# LED-zero20-SHIM.net
KiCad netlist of a schematic drawn in EAGLE
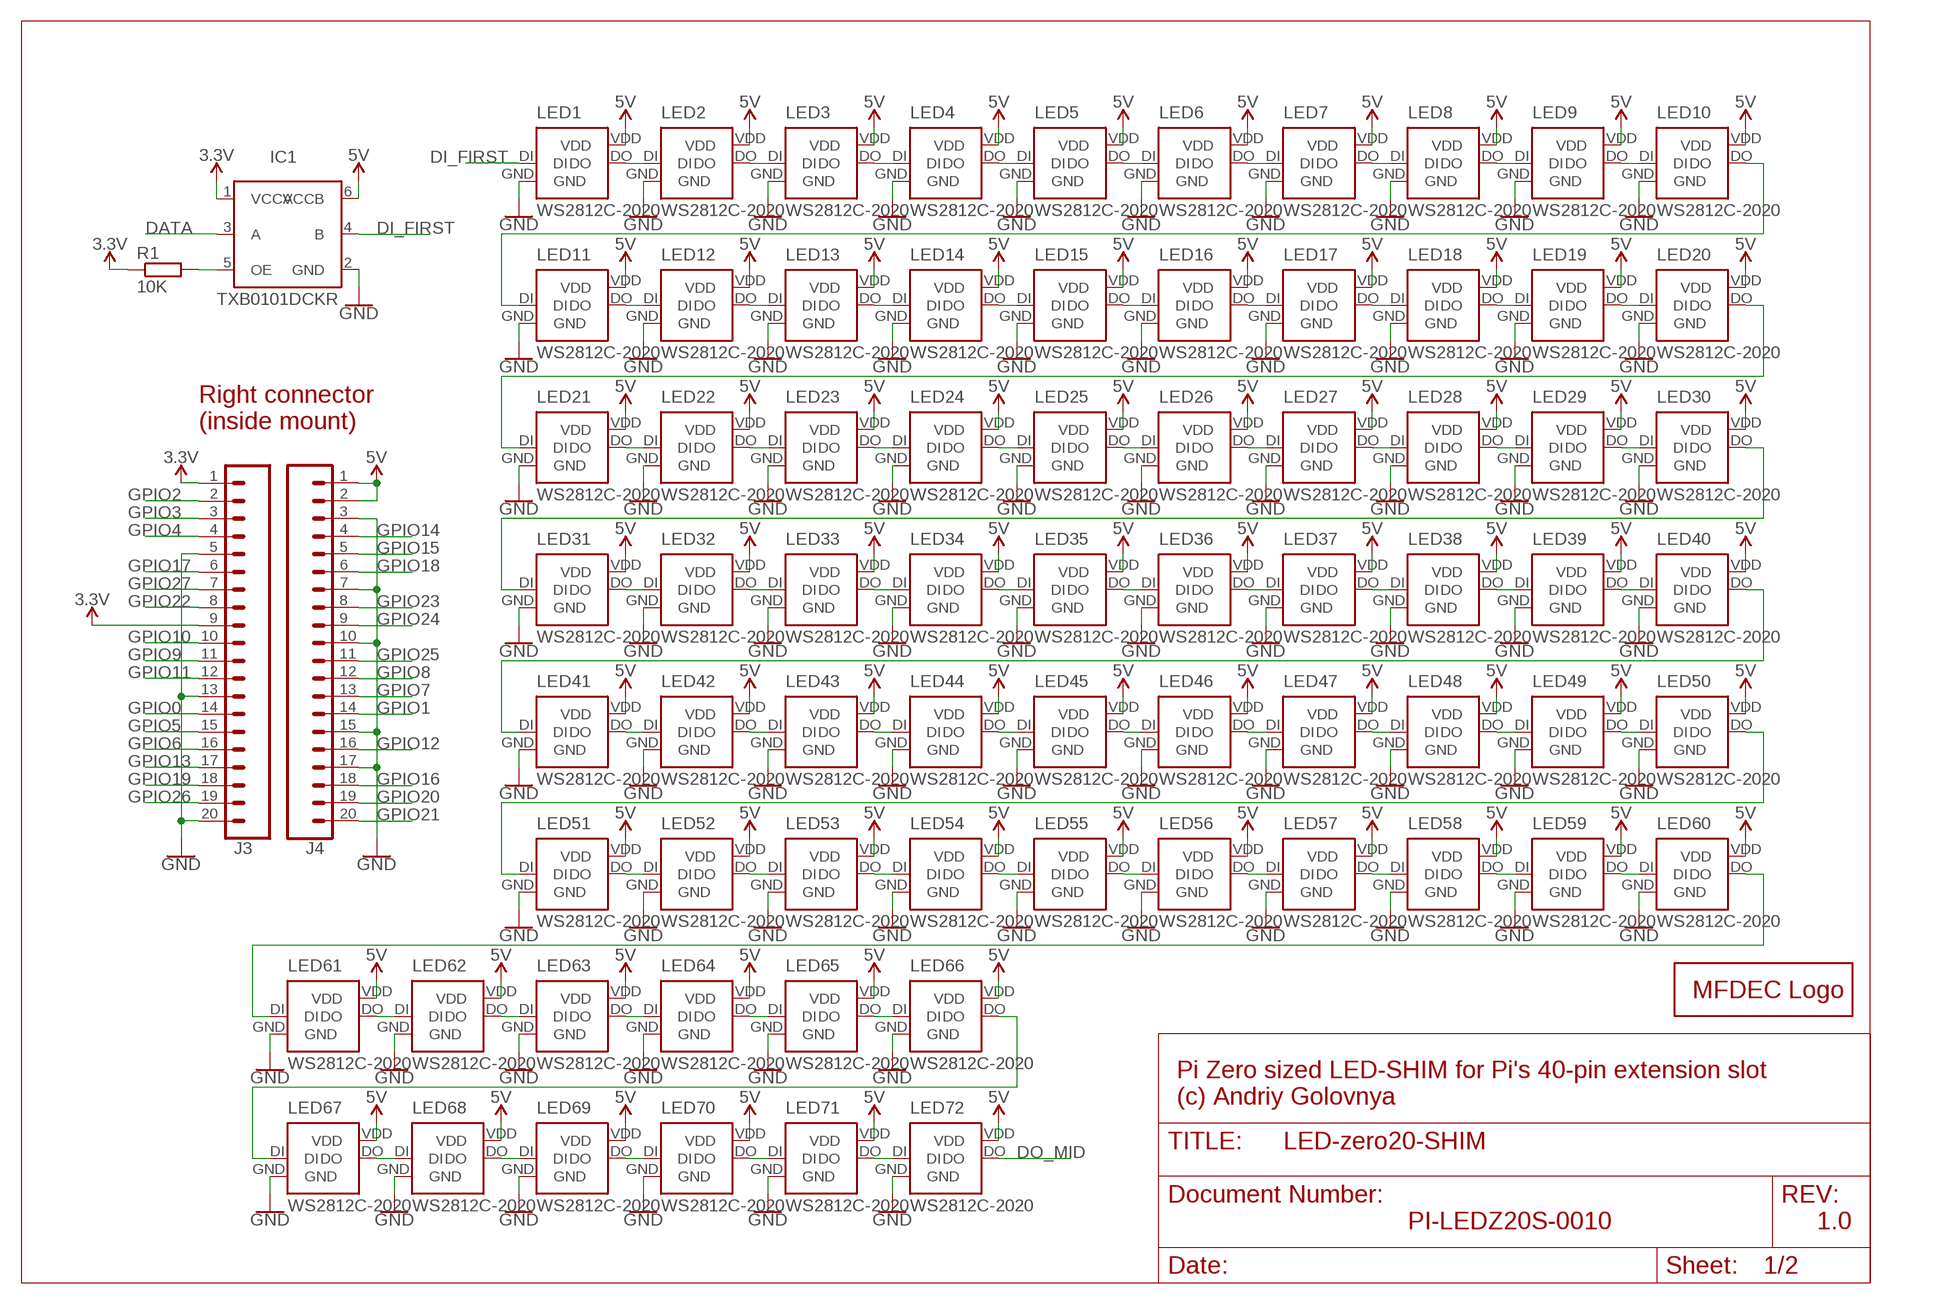
[diagram p0: schematic, sheet 1]
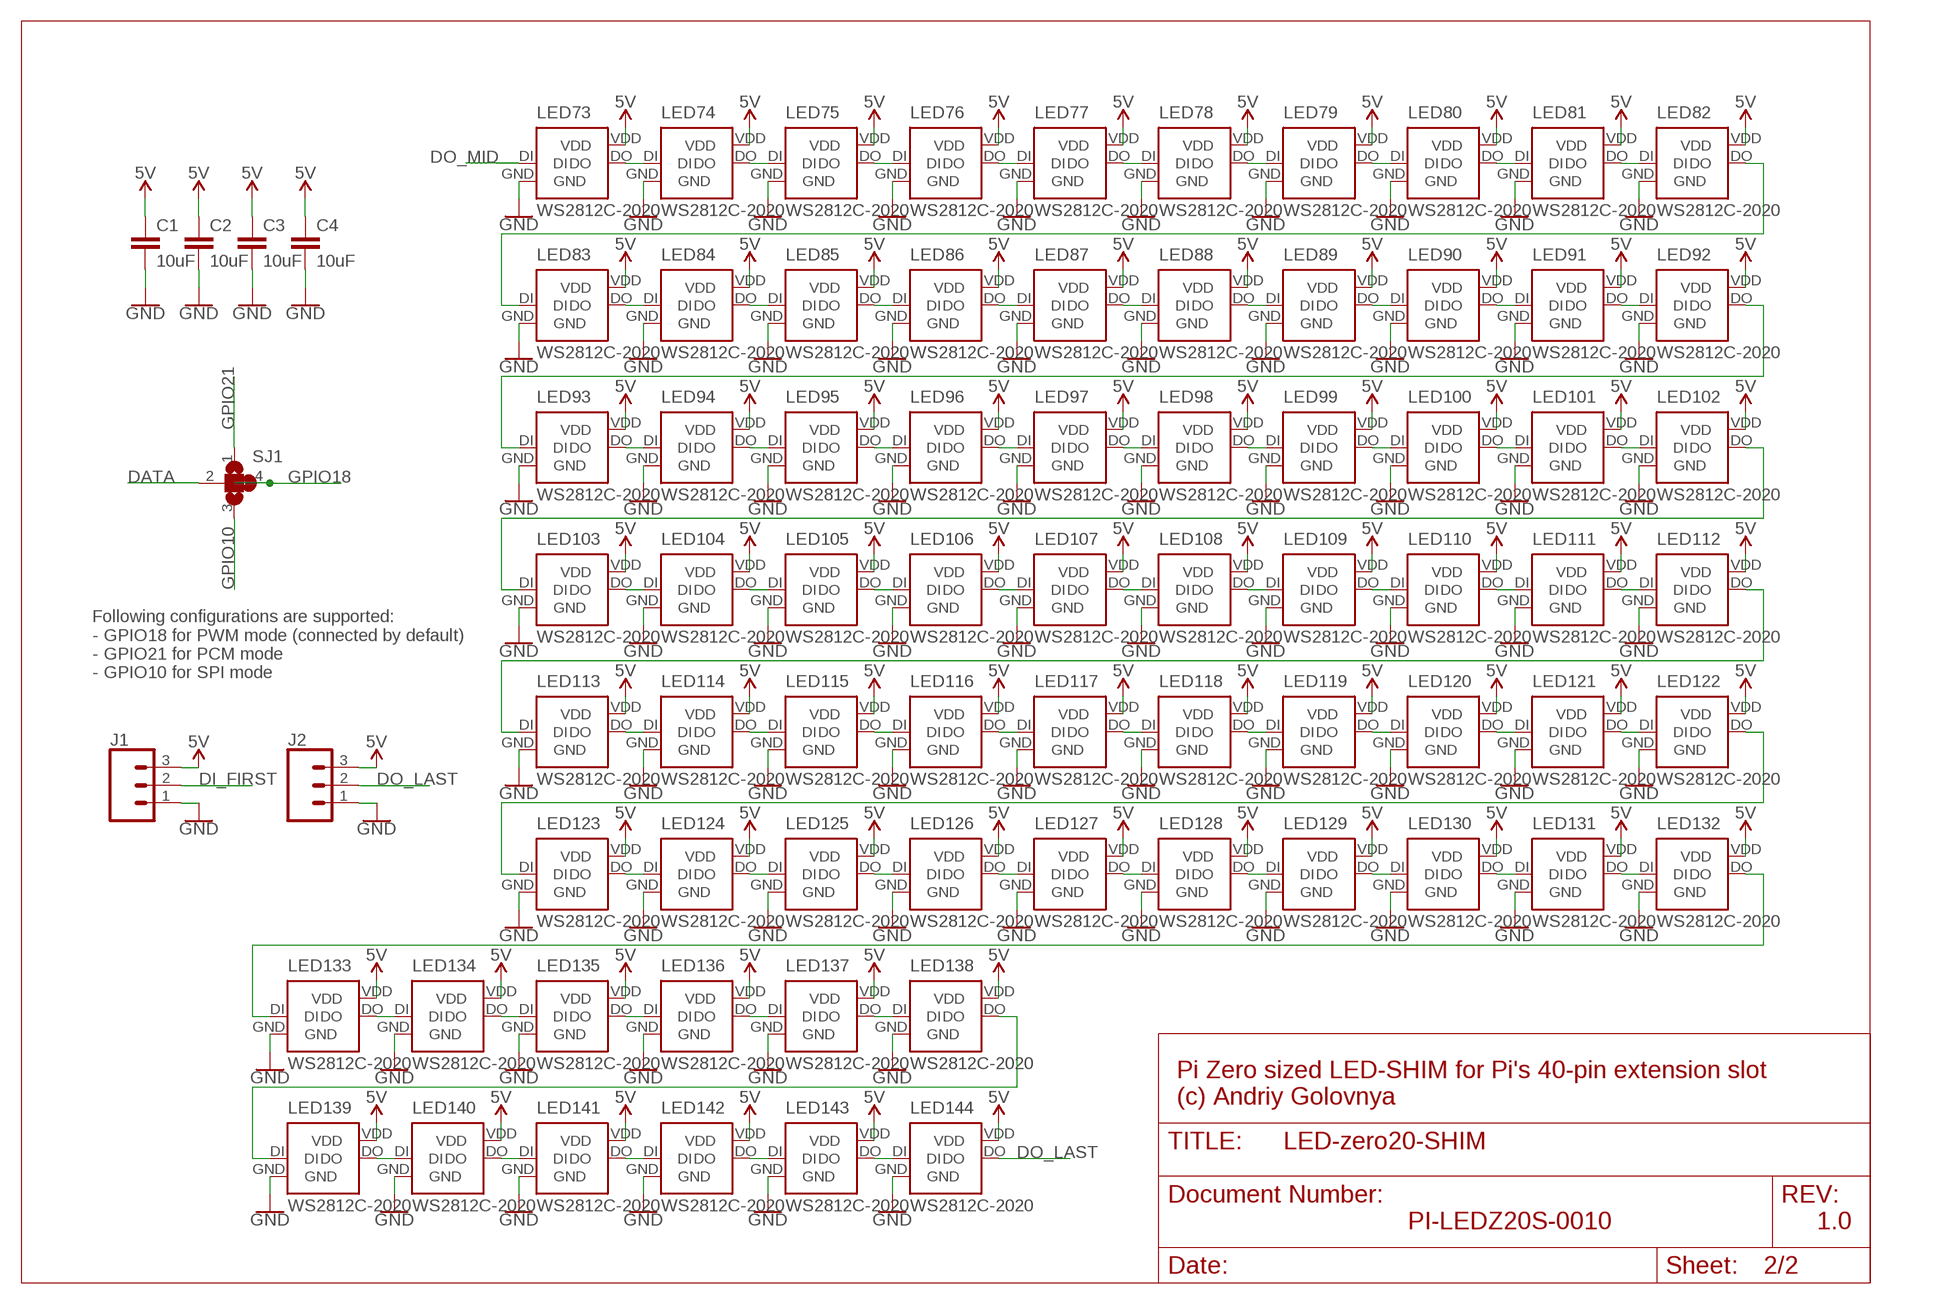
[diagram p1: schematic, sheet 2]

(export (version "E")
  (design (tool "Eeschema 10.0.6"))
  (components
    (comp (ref "IC1")
      (value "TXB0101DCKR")
      (footprint "eagle-import:SOT65P210X110-6N")
      (libsource (lib "eagle-import") (part "TXB0101DCKR"))
    )
    (comp (ref "J3")
      (value "CONN_20LOCK")
      (footprint "eagle-import:1X20_LOCK")
      (libsource (lib "eagle-import") (part "CONN_20LOCK"))
    )
    (comp (ref "J4")
      (value "CONN_20LOCK")
      (footprint "eagle-import:1X20_LOCK")
      (libsource (lib "eagle-import") (part "CONN_20LOCK"))
    )
    (comp (ref "LED1")
      (value "WS2812C-2020")
      (footprint "eagle-import:WS2812X-2020")
      (libsource (lib "eagle-import") (part "WS2812C-2020"))
    )
    (comp (ref "LED2")
      (value "WS2812C-2020")
      (footprint "eagle-import:WS2812X-2020")
      (libsource (lib "eagle-import") (part "WS2812C-2020"))
    )
    (comp (ref "LED3")
      (value "WS2812C-2020")
      (footprint "eagle-import:WS2812X-2020")
      (libsource (lib "eagle-import") (part "WS2812C-2020"))
    )
    (comp (ref "LED4")
      (value "WS2812C-2020")
      (footprint "eagle-import:WS2812X-2020")
      (libsource (lib "eagle-import") (part "WS2812C-2020"))
    )
    (comp (ref "LED5")
      (value "WS2812C-2020")
      (footprint "eagle-import:WS2812X-2020")
      (libsource (lib "eagle-import") (part "WS2812C-2020"))
    )
    (comp (ref "LED6")
      (value "WS2812C-2020")
      (footprint "eagle-import:WS2812X-2020")
      (libsource (lib "eagle-import") (part "WS2812C-2020"))
    )
    (comp (ref "LED7")
      (value "WS2812C-2020")
      (footprint "eagle-import:WS2812X-2020")
      (libsource (lib "eagle-import") (part "WS2812C-2020"))
    )
    (comp (ref "LED8")
      (value "WS2812C-2020")
      (footprint "eagle-import:WS2812X-2020")
      (libsource (lib "eagle-import") (part "WS2812C-2020"))
    )
    (comp (ref "LED9")
      (value "WS2812C-2020")
      (footprint "eagle-import:WS2812X-2020")
      (libsource (lib "eagle-import") (part "WS2812C-2020"))
    )
    (comp (ref "LED10")
      (value "WS2812C-2020")
      (footprint "eagle-import:WS2812X-2020")
      (libsource (lib "eagle-import") (part "WS2812C-2020"))
    )
    (comp (ref "LED11")
      (value "WS2812C-2020")
      (footprint "eagle-import:WS2812X-2020")
      (libsource (lib "eagle-import") (part "WS2812C-2020"))
    )
    (comp (ref "LED12")
      (value "WS2812C-2020")
      (footprint "eagle-import:WS2812X-2020")
      (libsource (lib "eagle-import") (part "WS2812C-2020"))
    )
    (comp (ref "LED13")
      (value "WS2812C-2020")
      (footprint "eagle-import:WS2812X-2020")
      (libsource (lib "eagle-import") (part "WS2812C-2020"))
    )
    (comp (ref "LED14")
      (value "WS2812C-2020")
      (footprint "eagle-import:WS2812X-2020")
      (libsource (lib "eagle-import") (part "WS2812C-2020"))
    )
    (comp (ref "LED15")
      (value "WS2812C-2020")
      (footprint "eagle-import:WS2812X-2020")
      (libsource (lib "eagle-import") (part "WS2812C-2020"))
    )
    (comp (ref "LED16")
      (value "WS2812C-2020")
      (footprint "eagle-import:WS2812X-2020")
      (libsource (lib "eagle-import") (part "WS2812C-2020"))
    )
    (comp (ref "LED17")
      (value "WS2812C-2020")
      (footprint "eagle-import:WS2812X-2020")
      (libsource (lib "eagle-import") (part "WS2812C-2020"))
    )
    (comp (ref "LED18")
      (value "WS2812C-2020")
      (footprint "eagle-import:WS2812X-2020")
      (libsource (lib "eagle-import") (part "WS2812C-2020"))
    )
    (comp (ref "LED19")
      (value "WS2812C-2020")
      (footprint "eagle-import:WS2812X-2020")
      (libsource (lib "eagle-import") (part "WS2812C-2020"))
    )
    (comp (ref "LED20")
      (value "WS2812C-2020")
      (footprint "eagle-import:WS2812X-2020")
      (libsource (lib "eagle-import") (part "WS2812C-2020"))
    )
    (comp (ref "LED21")
      (value "WS2812C-2020")
      (footprint "eagle-import:WS2812X-2020")
      (libsource (lib "eagle-import") (part "WS2812C-2020"))
    )
    (comp (ref "LED22")
      (value "WS2812C-2020")
      (footprint "eagle-import:WS2812X-2020")
      (libsource (lib "eagle-import") (part "WS2812C-2020"))
    )
    (comp (ref "LED23")
      (value "WS2812C-2020")
      (footprint "eagle-import:WS2812X-2020")
      (libsource (lib "eagle-import") (part "WS2812C-2020"))
    )
    (comp (ref "LED24")
      (value "WS2812C-2020")
      (footprint "eagle-import:WS2812X-2020")
      (libsource (lib "eagle-import") (part "WS2812C-2020"))
    )
    (comp (ref "LED25")
      (value "WS2812C-2020")
      (footprint "eagle-import:WS2812X-2020")
      (libsource (lib "eagle-import") (part "WS2812C-2020"))
    )
    (comp (ref "LED26")
      (value "WS2812C-2020")
      (footprint "eagle-import:WS2812X-2020")
      (libsource (lib "eagle-import") (part "WS2812C-2020"))
    )
    (comp (ref "LED27")
      (value "WS2812C-2020")
      (footprint "eagle-import:WS2812X-2020")
      (libsource (lib "eagle-import") (part "WS2812C-2020"))
    )
    (comp (ref "LED28")
      (value "WS2812C-2020")
      (footprint "eagle-import:WS2812X-2020")
      (libsource (lib "eagle-import") (part "WS2812C-2020"))
    )
    (comp (ref "LED29")
      (value "WS2812C-2020")
      (footprint "eagle-import:WS2812X-2020")
      (libsource (lib "eagle-import") (part "WS2812C-2020"))
    )
    (comp (ref "LED30")
      (value "WS2812C-2020")
      (footprint "eagle-import:WS2812X-2020")
      (libsource (lib "eagle-import") (part "WS2812C-2020"))
    )
    (comp (ref "LED31")
      (value "WS2812C-2020")
      (footprint "eagle-import:WS2812X-2020")
      (libsource (lib "eagle-import") (part "WS2812C-2020"))
    )
    (comp (ref "LED32")
      (value "WS2812C-2020")
      (footprint "eagle-import:WS2812X-2020")
      (libsource (lib "eagle-import") (part "WS2812C-2020"))
    )
    (comp (ref "LED33")
      (value "WS2812C-2020")
      (footprint "eagle-import:WS2812X-2020")
      (libsource (lib "eagle-import") (part "WS2812C-2020"))
    )
    (comp (ref "LED34")
      (value "WS2812C-2020")
      (footprint "eagle-import:WS2812X-2020")
      (libsource (lib "eagle-import") (part "WS2812C-2020"))
    )
    (comp (ref "LED35")
      (value "WS2812C-2020")
      (footprint "eagle-import:WS2812X-2020")
      (libsource (lib "eagle-import") (part "WS2812C-2020"))
    )
    (comp (ref "LED36")
      (value "WS2812C-2020")
      (footprint "eagle-import:WS2812X-2020")
      (libsource (lib "eagle-import") (part "WS2812C-2020"))
    )
    (comp (ref "LED37")
      (value "WS2812C-2020")
      (footprint "eagle-import:WS2812X-2020")
      (libsource (lib "eagle-import") (part "WS2812C-2020"))
    )
    (comp (ref "LED38")
      (value "WS2812C-2020")
      (footprint "eagle-import:WS2812X-2020")
      (libsource (lib "eagle-import") (part "WS2812C-2020"))
    )
    (comp (ref "LED39")
      (value "WS2812C-2020")
      (footprint "eagle-import:WS2812X-2020")
      (libsource (lib "eagle-import") (part "WS2812C-2020"))
    )
    (comp (ref "LED40")
      (value "WS2812C-2020")
      (footprint "eagle-import:WS2812X-2020")
      (libsource (lib "eagle-import") (part "WS2812C-2020"))
    )
    (comp (ref "LED41")
      (value "WS2812C-2020")
      (footprint "eagle-import:WS2812X-2020")
      (libsource (lib "eagle-import") (part "WS2812C-2020"))
    )
    (comp (ref "LED42")
      (value "WS2812C-2020")
      (footprint "eagle-import:WS2812X-2020")
      (libsource (lib "eagle-import") (part "WS2812C-2020"))
    )
    (comp (ref "LED43")
      (value "WS2812C-2020")
      (footprint "eagle-import:WS2812X-2020")
      (libsource (lib "eagle-import") (part "WS2812C-2020"))
    )
    (comp (ref "LED44")
      (value "WS2812C-2020")
      (footprint "eagle-import:WS2812X-2020")
      (libsource (lib "eagle-import") (part "WS2812C-2020"))
    )
    (comp (ref "LED45")
      (value "WS2812C-2020")
      (footprint "eagle-import:WS2812X-2020")
      (libsource (lib "eagle-import") (part "WS2812C-2020"))
    )
    (comp (ref "LED46")
      (value "WS2812C-2020")
      (footprint "eagle-import:WS2812X-2020")
      (libsource (lib "eagle-import") (part "WS2812C-2020"))
    )
    (comp (ref "LED47")
      (value "WS2812C-2020")
      (footprint "eagle-import:WS2812X-2020")
      (libsource (lib "eagle-import") (part "WS2812C-2020"))
    )
    (comp (ref "LED48")
      (value "WS2812C-2020")
      (footprint "eagle-import:WS2812X-2020")
      (libsource (lib "eagle-import") (part "WS2812C-2020"))
    )
    (comp (ref "LED49")
      (value "WS2812C-2020")
      (footprint "eagle-import:WS2812X-2020")
      (libsource (lib "eagle-import") (part "WS2812C-2020"))
    )
    (comp (ref "LED50")
      (value "WS2812C-2020")
      (footprint "eagle-import:WS2812X-2020")
      (libsource (lib "eagle-import") (part "WS2812C-2020"))
    )
    (comp (ref "LED51")
      (value "WS2812C-2020")
      (footprint "eagle-import:WS2812X-2020")
      (libsource (lib "eagle-import") (part "WS2812C-2020"))
    )
    (comp (ref "LED52")
      (value "WS2812C-2020")
      (footprint "eagle-import:WS2812X-2020")
      (libsource (lib "eagle-import") (part "WS2812C-2020"))
    )
    (comp (ref "LED53")
      (value "WS2812C-2020")
      (footprint "eagle-import:WS2812X-2020")
      (libsource (lib "eagle-import") (part "WS2812C-2020"))
    )
    (comp (ref "LED54")
      (value "WS2812C-2020")
      (footprint "eagle-import:WS2812X-2020")
      (libsource (lib "eagle-import") (part "WS2812C-2020"))
    )
    (comp (ref "LED55")
      (value "WS2812C-2020")
      (footprint "eagle-import:WS2812X-2020")
      (libsource (lib "eagle-import") (part "WS2812C-2020"))
    )
    (comp (ref "LED56")
      (value "WS2812C-2020")
      (footprint "eagle-import:WS2812X-2020")
      (libsource (lib "eagle-import") (part "WS2812C-2020"))
    )
    (comp (ref "LED57")
      (value "WS2812C-2020")
      (footprint "eagle-import:WS2812X-2020")
      (libsource (lib "eagle-import") (part "WS2812C-2020"))
    )
    (comp (ref "LED58")
      (value "WS2812C-2020")
      (footprint "eagle-import:WS2812X-2020")
      (libsource (lib "eagle-import") (part "WS2812C-2020"))
    )
    (comp (ref "LED59")
      (value "WS2812C-2020")
      (footprint "eagle-import:WS2812X-2020")
      (libsource (lib "eagle-import") (part "WS2812C-2020"))
    )
    (comp (ref "LED60")
      (value "WS2812C-2020")
      (footprint "eagle-import:WS2812X-2020")
      (libsource (lib "eagle-import") (part "WS2812C-2020"))
    )
    (comp (ref "LED61")
      (value "WS2812C-2020")
      (footprint "eagle-import:WS2812X-2020")
      (libsource (lib "eagle-import") (part "WS2812C-2020"))
    )
    (comp (ref "LED62")
      (value "WS2812C-2020")
      (footprint "eagle-import:WS2812X-2020")
      (libsource (lib "eagle-import") (part "WS2812C-2020"))
    )
    (comp (ref "LED63")
      (value "WS2812C-2020")
      (footprint "eagle-import:WS2812X-2020")
      (libsource (lib "eagle-import") (part "WS2812C-2020"))
    )
    (comp (ref "LED64")
      (value "WS2812C-2020")
      (footprint "eagle-import:WS2812X-2020")
      (libsource (lib "eagle-import") (part "WS2812C-2020"))
    )
    (comp (ref "LED65")
      (value "WS2812C-2020")
      (footprint "eagle-import:WS2812X-2020")
      (libsource (lib "eagle-import") (part "WS2812C-2020"))
    )
    (comp (ref "LED66")
      (value "WS2812C-2020")
      (footprint "eagle-import:WS2812X-2020")
      (libsource (lib "eagle-import") (part "WS2812C-2020"))
    )
    (comp (ref "LED67")
      (value "WS2812C-2020")
      (footprint "eagle-import:WS2812X-2020")
      (libsource (lib "eagle-import") (part "WS2812C-2020"))
    )
    (comp (ref "LED68")
      (value "WS2812C-2020")
      (footprint "eagle-import:WS2812X-2020")
      (libsource (lib "eagle-import") (part "WS2812C-2020"))
    )
    (comp (ref "LED69")
      (value "WS2812C-2020")
      (footprint "eagle-import:WS2812X-2020")
      (libsource (lib "eagle-import") (part "WS2812C-2020"))
    )
    (comp (ref "LED70")
      (value "WS2812C-2020")
      (footprint "eagle-import:WS2812X-2020")
      (libsource (lib "eagle-import") (part "WS2812C-2020"))
    )
    (comp (ref "LED71")
      (value "WS2812C-2020")
      (footprint "eagle-import:WS2812X-2020")
      (libsource (lib "eagle-import") (part "WS2812C-2020"))
    )
    (comp (ref "LED72")
      (value "WS2812C-2020")
      (footprint "eagle-import:WS2812X-2020")
      (libsource (lib "eagle-import") (part "WS2812C-2020"))
    )
    (comp (ref "LOGO1")
      (value "MFDECLOGO_L_30MM")
      (footprint "eagle-import:MFDEC_L_30MM")
      (libsource (lib "eagle-import") (part "MFDECLOGO_L_30MM"))
    )
    (comp (ref "R1")
      (value "10K")
      (footprint "eagle-import:R0402")
      (libsource (lib "eagle-import") (part "R-EU_R0402"))
    )
    (comp (ref "C1")
      (value "10uF")
      (footprint "eagle-import:C0805")
      (libsource (lib "eagle-import") (part "C-EUC0805"))
    )
    (comp (ref "C2")
      (value "10uF")
      (footprint "eagle-import:C0805")
      (libsource (lib "eagle-import") (part "C-EUC0805"))
    )
    (comp (ref "C3")
      (value "10uF")
      (footprint "eagle-import:C0805")
      (libsource (lib "eagle-import") (part "C-EUC0805"))
    )
    (comp (ref "C4")
      (value "10uF")
      (footprint "eagle-import:C0805")
      (libsource (lib "eagle-import") (part "C-EUC0805"))
    )
    (comp (ref "J1")
      (value "CONN_03")
      (footprint "eagle-import:1X03")
      (libsource (lib "eagle-import") (part "CONN_03"))
    )
    (comp (ref "J2")
      (value "CONN_03")
      (footprint "eagle-import:1X03")
      (libsource (lib "eagle-import") (part "CONN_03"))
    )
    (comp (ref "LED73")
      (value "WS2812C-2020")
      (footprint "eagle-import:WS2812X-2020")
      (libsource (lib "eagle-import") (part "WS2812C-2020"))
    )
    (comp (ref "LED74")
      (value "WS2812C-2020")
      (footprint "eagle-import:WS2812X-2020")
      (libsource (lib "eagle-import") (part "WS2812C-2020"))
    )
    (comp (ref "LED75")
      (value "WS2812C-2020")
      (footprint "eagle-import:WS2812X-2020")
      (libsource (lib "eagle-import") (part "WS2812C-2020"))
    )
    (comp (ref "LED76")
      (value "WS2812C-2020")
      (footprint "eagle-import:WS2812X-2020")
      (libsource (lib "eagle-import") (part "WS2812C-2020"))
    )
    (comp (ref "LED77")
      (value "WS2812C-2020")
      (footprint "eagle-import:WS2812X-2020")
      (libsource (lib "eagle-import") (part "WS2812C-2020"))
    )
    (comp (ref "LED78")
      (value "WS2812C-2020")
      (footprint "eagle-import:WS2812X-2020")
      (libsource (lib "eagle-import") (part "WS2812C-2020"))
    )
    (comp (ref "LED79")
      (value "WS2812C-2020")
      (footprint "eagle-import:WS2812X-2020")
      (libsource (lib "eagle-import") (part "WS2812C-2020"))
    )
    (comp (ref "LED80")
      (value "WS2812C-2020")
      (footprint "eagle-import:WS2812X-2020")
      (libsource (lib "eagle-import") (part "WS2812C-2020"))
    )
    (comp (ref "LED81")
      (value "WS2812C-2020")
      (footprint "eagle-import:WS2812X-2020")
      (libsource (lib "eagle-import") (part "WS2812C-2020"))
    )
    (comp (ref "LED82")
      (value "WS2812C-2020")
      (footprint "eagle-import:WS2812X-2020")
      (libsource (lib "eagle-import") (part "WS2812C-2020"))
    )
    (comp (ref "LED83")
      (value "WS2812C-2020")
      (footprint "eagle-import:WS2812X-2020")
      (libsource (lib "eagle-import") (part "WS2812C-2020"))
    )
    (comp (ref "LED84")
      (value "WS2812C-2020")
      (footprint "eagle-import:WS2812X-2020")
      (libsource (lib "eagle-import") (part "WS2812C-2020"))
    )
    (comp (ref "LED85")
      (value "WS2812C-2020")
      (footprint "eagle-import:WS2812X-2020")
      (libsource (lib "eagle-import") (part "WS2812C-2020"))
    )
    (comp (ref "LED86")
      (value "WS2812C-2020")
      (footprint "eagle-import:WS2812X-2020")
      (libsource (lib "eagle-import") (part "WS2812C-2020"))
    )
    (comp (ref "LED87")
      (value "WS2812C-2020")
      (footprint "eagle-import:WS2812X-2020")
      (libsource (lib "eagle-import") (part "WS2812C-2020"))
    )
    (comp (ref "LED88")
      (value "WS2812C-2020")
      (footprint "eagle-import:WS2812X-2020")
      (libsource (lib "eagle-import") (part "WS2812C-2020"))
    )
    (comp (ref "LED89")
      (value "WS2812C-2020")
      (footprint "eagle-import:WS2812X-2020")
      (libsource (lib "eagle-import") (part "WS2812C-2020"))
    )
    (comp (ref "LED90")
      (value "WS2812C-2020")
      (footprint "eagle-import:WS2812X-2020")
      (libsource (lib "eagle-import") (part "WS2812C-2020"))
    )
    (comp (ref "LED91")
      (value "WS2812C-2020")
      (footprint "eagle-import:WS2812X-2020")
      (libsource (lib "eagle-import") (part "WS2812C-2020"))
    )
    (comp (ref "LED92")
      (value "WS2812C-2020")
      (footprint "eagle-import:WS2812X-2020")
      (libsource (lib "eagle-import") (part "WS2812C-2020"))
    )
    (comp (ref "LED93")
      (value "WS2812C-2020")
      (footprint "eagle-import:WS2812X-2020")
      (libsource (lib "eagle-import") (part "WS2812C-2020"))
    )
    (comp (ref "LED94")
      (value "WS2812C-2020")
      (footprint "eagle-import:WS2812X-2020")
      (libsource (lib "eagle-import") (part "WS2812C-2020"))
    )
    (comp (ref "LED95")
      (value "WS2812C-2020")
      (footprint "eagle-import:WS2812X-2020")
      (libsource (lib "eagle-import") (part "WS2812C-2020"))
    )
    (comp (ref "LED96")
      (value "WS2812C-2020")
      (footprint "eagle-import:WS2812X-2020")
      (libsource (lib "eagle-import") (part "WS2812C-2020"))
    )
    (comp (ref "LED97")
      (value "WS2812C-2020")
      (footprint "eagle-import:WS2812X-2020")
      (libsource (lib "eagle-import") (part "WS2812C-2020"))
    )
    (comp (ref "LED98")
      (value "WS2812C-2020")
      (footprint "eagle-import:WS2812X-2020")
      (libsource (lib "eagle-import") (part "WS2812C-2020"))
    )
    (comp (ref "LED99")
      (value "WS2812C-2020")
      (footprint "eagle-import:WS2812X-2020")
      (libsource (lib "eagle-import") (part "WS2812C-2020"))
    )
    (comp (ref "LED100")
      (value "WS2812C-2020")
      (footprint "eagle-import:WS2812X-2020")
      (libsource (lib "eagle-import") (part "WS2812C-2020"))
    )
    (comp (ref "LED101")
      (value "WS2812C-2020")
      (footprint "eagle-import:WS2812X-2020")
      (libsource (lib "eagle-import") (part "WS2812C-2020"))
    )
    (comp (ref "LED102")
      (value "WS2812C-2020")
      (footprint "eagle-import:WS2812X-2020")
      (libsource (lib "eagle-import") (part "WS2812C-2020"))
    )
    (comp (ref "LED103")
      (value "WS2812C-2020")
      (footprint "eagle-import:WS2812X-2020")
      (libsource (lib "eagle-import") (part "WS2812C-2020"))
    )
    (comp (ref "LED104")
      (value "WS2812C-2020")
      (footprint "eagle-import:WS2812X-2020")
      (libsource (lib "eagle-import") (part "WS2812C-2020"))
    )
    (comp (ref "LED105")
      (value "WS2812C-2020")
      (footprint "eagle-import:WS2812X-2020")
      (libsource (lib "eagle-import") (part "WS2812C-2020"))
    )
    (comp (ref "LED106")
      (value "WS2812C-2020")
      (footprint "eagle-import:WS2812X-2020")
      (libsource (lib "eagle-import") (part "WS2812C-2020"))
    )
    (comp (ref "LED107")
      (value "WS2812C-2020")
      (footprint "eagle-import:WS2812X-2020")
      (libsource (lib "eagle-import") (part "WS2812C-2020"))
    )
    (comp (ref "LED108")
      (value "WS2812C-2020")
      (footprint "eagle-import:WS2812X-2020")
      (libsource (lib "eagle-import") (part "WS2812C-2020"))
    )
    (comp (ref "LED109")
      (value "WS2812C-2020")
      (footprint "eagle-import:WS2812X-2020")
      (libsource (lib "eagle-import") (part "WS2812C-2020"))
    )
    (comp (ref "LED110")
      (value "WS2812C-2020")
      (footprint "eagle-import:WS2812X-2020")
      (libsource (lib "eagle-import") (part "WS2812C-2020"))
    )
    (comp (ref "LED111")
      (value "WS2812C-2020")
      (footprint "eagle-import:WS2812X-2020")
      (libsource (lib "eagle-import") (part "WS2812C-2020"))
    )
    (comp (ref "LED112")
      (value "WS2812C-2020")
      (footprint "eagle-import:WS2812X-2020")
      (libsource (lib "eagle-import") (part "WS2812C-2020"))
    )
    (comp (ref "LED113")
      (value "WS2812C-2020")
      (footprint "eagle-import:WS2812X-2020")
      (libsource (lib "eagle-import") (part "WS2812C-2020"))
    )
    (comp (ref "LED114")
      (value "WS2812C-2020")
      (footprint "eagle-import:WS2812X-2020")
      (libsource (lib "eagle-import") (part "WS2812C-2020"))
    )
    (comp (ref "LED115")
      (value "WS2812C-2020")
      (footprint "eagle-import:WS2812X-2020")
      (libsource (lib "eagle-import") (part "WS2812C-2020"))
    )
    (comp (ref "LED116")
      (value "WS2812C-2020")
      (footprint "eagle-import:WS2812X-2020")
      (libsource (lib "eagle-import") (part "WS2812C-2020"))
    )
    (comp (ref "LED117")
      (value "WS2812C-2020")
      (footprint "eagle-import:WS2812X-2020")
      (libsource (lib "eagle-import") (part "WS2812C-2020"))
    )
    (comp (ref "LED118")
      (value "WS2812C-2020")
      (footprint "eagle-import:WS2812X-2020")
      (libsource (lib "eagle-import") (part "WS2812C-2020"))
    )
    (comp (ref "LED119")
      (value "WS2812C-2020")
      (footprint "eagle-import:WS2812X-2020")
      (libsource (lib "eagle-import") (part "WS2812C-2020"))
    )
    (comp (ref "LED120")
      (value "WS2812C-2020")
      (footprint "eagle-import:WS2812X-2020")
      (libsource (lib "eagle-import") (part "WS2812C-2020"))
    )
    (comp (ref "LED121")
      (value "WS2812C-2020")
      (footprint "eagle-import:WS2812X-2020")
      (libsource (lib "eagle-import") (part "WS2812C-2020"))
    )
    (comp (ref "LED122")
      (value "WS2812C-2020")
      (footprint "eagle-import:WS2812X-2020")
      (libsource (lib "eagle-import") (part "WS2812C-2020"))
    )
    (comp (ref "LED123")
      (value "WS2812C-2020")
      (footprint "eagle-import:WS2812X-2020")
      (libsource (lib "eagle-import") (part "WS2812C-2020"))
    )
    (comp (ref "LED124")
      (value "WS2812C-2020")
      (footprint "eagle-import:WS2812X-2020")
      (libsource (lib "eagle-import") (part "WS2812C-2020"))
    )
    (comp (ref "LED125")
      (value "WS2812C-2020")
      (footprint "eagle-import:WS2812X-2020")
      (libsource (lib "eagle-import") (part "WS2812C-2020"))
    )
    (comp (ref "LED126")
      (value "WS2812C-2020")
      (footprint "eagle-import:WS2812X-2020")
      (libsource (lib "eagle-import") (part "WS2812C-2020"))
    )
    (comp (ref "LED127")
      (value "WS2812C-2020")
      (footprint "eagle-import:WS2812X-2020")
      (libsource (lib "eagle-import") (part "WS2812C-2020"))
    )
    (comp (ref "LED128")
      (value "WS2812C-2020")
      (footprint "eagle-import:WS2812X-2020")
      (libsource (lib "eagle-import") (part "WS2812C-2020"))
    )
    (comp (ref "LED129")
      (value "WS2812C-2020")
      (footprint "eagle-import:WS2812X-2020")
      (libsource (lib "eagle-import") (part "WS2812C-2020"))
    )
    (comp (ref "LED130")
      (value "WS2812C-2020")
      (footprint "eagle-import:WS2812X-2020")
      (libsource (lib "eagle-import") (part "WS2812C-2020"))
    )
    (comp (ref "LED131")
      (value "WS2812C-2020")
      (footprint "eagle-import:WS2812X-2020")
      (libsource (lib "eagle-import") (part "WS2812C-2020"))
    )
    (comp (ref "LED132")
      (value "WS2812C-2020")
      (footprint "eagle-import:WS2812X-2020")
      (libsource (lib "eagle-import") (part "WS2812C-2020"))
    )
    (comp (ref "LED133")
      (value "WS2812C-2020")
      (footprint "eagle-import:WS2812X-2020")
      (libsource (lib "eagle-import") (part "WS2812C-2020"))
    )
    (comp (ref "LED134")
      (value "WS2812C-2020")
      (footprint "eagle-import:WS2812X-2020")
      (libsource (lib "eagle-import") (part "WS2812C-2020"))
    )
    (comp (ref "LED135")
      (value "WS2812C-2020")
      (footprint "eagle-import:WS2812X-2020")
      (libsource (lib "eagle-import") (part "WS2812C-2020"))
    )
    (comp (ref "LED136")
      (value "WS2812C-2020")
      (footprint "eagle-import:WS2812X-2020")
      (libsource (lib "eagle-import") (part "WS2812C-2020"))
    )
    (comp (ref "LED137")
      (value "WS2812C-2020")
      (footprint "eagle-import:WS2812X-2020")
      (libsource (lib "eagle-import") (part "WS2812C-2020"))
    )
    (comp (ref "LED138")
      (value "WS2812C-2020")
      (footprint "eagle-import:WS2812X-2020")
      (libsource (lib "eagle-import") (part "WS2812C-2020"))
    )
    (comp (ref "LED139")
      (value "WS2812C-2020")
      (footprint "eagle-import:WS2812X-2020")
      (libsource (lib "eagle-import") (part "WS2812C-2020"))
    )
    (comp (ref "LED140")
      (value "WS2812C-2020")
      (footprint "eagle-import:WS2812X-2020")
      (libsource (lib "eagle-import") (part "WS2812C-2020"))
    )
    (comp (ref "LED141")
      (value "WS2812C-2020")
      (footprint "eagle-import:WS2812X-2020")
      (libsource (lib "eagle-import") (part "WS2812C-2020"))
    )
    (comp (ref "LED142")
      (value "WS2812C-2020")
      (footprint "eagle-import:WS2812X-2020")
      (libsource (lib "eagle-import") (part "WS2812C-2020"))
    )
    (comp (ref "LED143")
      (value "WS2812C-2020")
      (footprint "eagle-import:WS2812X-2020")
      (libsource (lib "eagle-import") (part "WS2812C-2020"))
    )
    (comp (ref "LED144")
      (value "WS2812C-2020")
      (footprint "eagle-import:WS2812X-2020")
      (libsource (lib "eagle-import") (part "WS2812C-2020"))
    )
    (comp (ref "SJ1")
      (value "SJ3")
      (footprint "eagle-import:SJ_3")
      (libsource (lib "eagle-import") (part "SJ3"))
    )
  )
  (nets
    (net (code "1") (name "3.3V") (class "Default")
      (node (ref "IC1") (pin "1") (pinfunction "VCCA_1") (pintype "power_in"))
      (node (ref "J3") (pin "1") (pinfunction "1_1") (pintype "passive"))
      (node (ref "J3") (pin "9") (pinfunction "9_9") (pintype "passive"))
      (node (ref "R1") (pin "1") (pinfunction "1_1") (pintype "passive"))
    )
    (net (code "2") (name "5V") (class "Default")
      (node (ref "C1") (pin "1") (pinfunction "1_1") (pintype "passive"))
      (node (ref "C2") (pin "1") (pinfunction "1_1") (pintype "passive"))
      (node (ref "C3") (pin "1") (pinfunction "1_1") (pintype "passive"))
      (node (ref "C4") (pin "1") (pinfunction "1_1") (pintype "passive"))
      (node (ref "IC1") (pin "6") (pinfunction "VCCB_6") (pintype "power_in"))
      (node (ref "J1") (pin "3") (pinfunction "3_3") (pintype "passive"))
      (node (ref "J2") (pin "3") (pinfunction "3_3") (pintype "passive"))
      (node (ref "J4") (pin "1") (pinfunction "1_1") (pintype "passive"))
      (node (ref "J4") (pin "2") (pinfunction "2_2") (pintype "passive"))
      (node (ref "LED1") (pin "VDD") (pinfunction "VDD_VDD") (pintype "power_in"))
      (node (ref "LED10") (pin "VDD") (pinfunction "VDD_VDD") (pintype "power_in"))
      (node (ref "LED100") (pin "VDD") (pinfunction "VDD_VDD") (pintype "power_in"))
      (node (ref "LED101") (pin "VDD") (pinfunction "VDD_VDD") (pintype "power_in"))
      (node (ref "LED102") (pin "VDD") (pinfunction "VDD_VDD") (pintype "power_in"))
      (node (ref "LED103") (pin "VDD") (pinfunction "VDD_VDD") (pintype "power_in"))
      (node (ref "LED104") (pin "VDD") (pinfunction "VDD_VDD") (pintype "power_in"))
      (node (ref "LED105") (pin "VDD") (pinfunction "VDD_VDD") (pintype "power_in"))
      (node (ref "LED106") (pin "VDD") (pinfunction "VDD_VDD") (pintype "power_in"))
      (node (ref "LED107") (pin "VDD") (pinfunction "VDD_VDD") (pintype "power_in"))
      (node (ref "LED108") (pin "VDD") (pinfunction "VDD_VDD") (pintype "power_in"))
      (node (ref "LED109") (pin "VDD") (pinfunction "VDD_VDD") (pintype "power_in"))
      (node (ref "LED11") (pin "VDD") (pinfunction "VDD_VDD") (pintype "power_in"))
      (node (ref "LED110") (pin "VDD") (pinfunction "VDD_VDD") (pintype "power_in"))
      (node (ref "LED111") (pin "VDD") (pinfunction "VDD_VDD") (pintype "power_in"))
      (node (ref "LED112") (pin "VDD") (pinfunction "VDD_VDD") (pintype "power_in"))
      (node (ref "LED113") (pin "VDD") (pinfunction "VDD_VDD") (pintype "power_in"))
      (node (ref "LED114") (pin "VDD") (pinfunction "VDD_VDD") (pintype "power_in"))
      (node (ref "LED115") (pin "VDD") (pinfunction "VDD_VDD") (pintype "power_in"))
      (node (ref "LED116") (pin "VDD") (pinfunction "VDD_VDD") (pintype "power_in"))
      (node (ref "LED117") (pin "VDD") (pinfunction "VDD_VDD") (pintype "power_in"))
      (node (ref "LED118") (pin "VDD") (pinfunction "VDD_VDD") (pintype "power_in"))
      (node (ref "LED119") (pin "VDD") (pinfunction "VDD_VDD") (pintype "power_in"))
      (node (ref "LED12") (pin "VDD") (pinfunction "VDD_VDD") (pintype "power_in"))
      (node (ref "LED120") (pin "VDD") (pinfunction "VDD_VDD") (pintype "power_in"))
      (node (ref "LED121") (pin "VDD") (pinfunction "VDD_VDD") (pintype "power_in"))
      (node (ref "LED122") (pin "VDD") (pinfunction "VDD_VDD") (pintype "power_in"))
      (node (ref "LED123") (pin "VDD") (pinfunction "VDD_VDD") (pintype "power_in"))
      (node (ref "LED124") (pin "VDD") (pinfunction "VDD_VDD") (pintype "power_in"))
      (node (ref "LED125") (pin "VDD") (pinfunction "VDD_VDD") (pintype "power_in"))
      (node (ref "LED126") (pin "VDD") (pinfunction "VDD_VDD") (pintype "power_in"))
      (node (ref "LED127") (pin "VDD") (pinfunction "VDD_VDD") (pintype "power_in"))
      (node (ref "LED128") (pin "VDD") (pinfunction "VDD_VDD") (pintype "power_in"))
      (node (ref "LED129") (pin "VDD") (pinfunction "VDD_VDD") (pintype "power_in"))
      (node (ref "LED13") (pin "VDD") (pinfunction "VDD_VDD") (pintype "power_in"))
      (node (ref "LED130") (pin "VDD") (pinfunction "VDD_VDD") (pintype "power_in"))
      (node (ref "LED131") (pin "VDD") (pinfunction "VDD_VDD") (pintype "power_in"))
      (node (ref "LED132") (pin "VDD") (pinfunction "VDD_VDD") (pintype "power_in"))
      (node (ref "LED133") (pin "VDD") (pinfunction "VDD_VDD") (pintype "power_in"))
      (node (ref "LED134") (pin "VDD") (pinfunction "VDD_VDD") (pintype "power_in"))
      (node (ref "LED135") (pin "VDD") (pinfunction "VDD_VDD") (pintype "power_in"))
      (node (ref "LED136") (pin "VDD") (pinfunction "VDD_VDD") (pintype "power_in"))
      (node (ref "LED137") (pin "VDD") (pinfunction "VDD_VDD") (pintype "power_in"))
      (node (ref "LED138") (pin "VDD") (pinfunction "VDD_VDD") (pintype "power_in"))
      (node (ref "LED139") (pin "VDD") (pinfunction "VDD_VDD") (pintype "power_in"))
      (node (ref "LED14") (pin "VDD") (pinfunction "VDD_VDD") (pintype "power_in"))
      (node (ref "LED140") (pin "VDD") (pinfunction "VDD_VDD") (pintype "power_in"))
      (node (ref "LED141") (pin "VDD") (pinfunction "VDD_VDD") (pintype "power_in"))
      (node (ref "LED142") (pin "VDD") (pinfunction "VDD_VDD") (pintype "power_in"))
      (node (ref "LED143") (pin "VDD") (pinfunction "VDD_VDD") (pintype "power_in"))
      (node (ref "LED144") (pin "VDD") (pinfunction "VDD_VDD") (pintype "power_in"))
      (node (ref "LED15") (pin "VDD") (pinfunction "VDD_VDD") (pintype "power_in"))
      (node (ref "LED16") (pin "VDD") (pinfunction "VDD_VDD") (pintype "power_in"))
      (node (ref "LED17") (pin "VDD") (pinfunction "VDD_VDD") (pintype "power_in"))
      (node (ref "LED18") (pin "VDD") (pinfunction "VDD_VDD") (pintype "power_in"))
      (node (ref "LED19") (pin "VDD") (pinfunction "VDD_VDD") (pintype "power_in"))
      (node (ref "LED2") (pin "VDD") (pinfunction "VDD_VDD") (pintype "power_in"))
      (node (ref "LED20") (pin "VDD") (pinfunction "VDD_VDD") (pintype "power_in"))
      (node (ref "LED21") (pin "VDD") (pinfunction "VDD_VDD") (pintype "power_in"))
      (node (ref "LED22") (pin "VDD") (pinfunction "VDD_VDD") (pintype "power_in"))
      (node (ref "LED23") (pin "VDD") (pinfunction "VDD_VDD") (pintype "power_in"))
      (node (ref "LED24") (pin "VDD") (pinfunction "VDD_VDD") (pintype "power_in"))
      (node (ref "LED25") (pin "VDD") (pinfunction "VDD_VDD") (pintype "power_in"))
      (node (ref "LED26") (pin "VDD") (pinfunction "VDD_VDD") (pintype "power_in"))
      (node (ref "LED27") (pin "VDD") (pinfunction "VDD_VDD") (pintype "power_in"))
      (node (ref "LED28") (pin "VDD") (pinfunction "VDD_VDD") (pintype "power_in"))
      (node (ref "LED29") (pin "VDD") (pinfunction "VDD_VDD") (pintype "power_in"))
      (node (ref "LED3") (pin "VDD") (pinfunction "VDD_VDD") (pintype "power_in"))
      (node (ref "LED30") (pin "VDD") (pinfunction "VDD_VDD") (pintype "power_in"))
      (node (ref "LED31") (pin "VDD") (pinfunction "VDD_VDD") (pintype "power_in"))
      (node (ref "LED32") (pin "VDD") (pinfunction "VDD_VDD") (pintype "power_in"))
      (node (ref "LED33") (pin "VDD") (pinfunction "VDD_VDD") (pintype "power_in"))
      (node (ref "LED34") (pin "VDD") (pinfunction "VDD_VDD") (pintype "power_in"))
      (node (ref "LED35") (pin "VDD") (pinfunction "VDD_VDD") (pintype "power_in"))
      (node (ref "LED36") (pin "VDD") (pinfunction "VDD_VDD") (pintype "power_in"))
      (node (ref "LED37") (pin "VDD") (pinfunction "VDD_VDD") (pintype "power_in"))
      (node (ref "LED38") (pin "VDD") (pinfunction "VDD_VDD") (pintype "power_in"))
      (node (ref "LED39") (pin "VDD") (pinfunction "VDD_VDD") (pintype "power_in"))
      (node (ref "LED4") (pin "VDD") (pinfunction "VDD_VDD") (pintype "power_in"))
      (node (ref "LED40") (pin "VDD") (pinfunction "VDD_VDD") (pintype "power_in"))
      (node (ref "LED41") (pin "VDD") (pinfunction "VDD_VDD") (pintype "power_in"))
      (node (ref "LED42") (pin "VDD") (pinfunction "VDD_VDD") (pintype "power_in"))
      (node (ref "LED43") (pin "VDD") (pinfunction "VDD_VDD") (pintype "power_in"))
      (node (ref "LED44") (pin "VDD") (pinfunction "VDD_VDD") (pintype "power_in"))
      (node (ref "LED45") (pin "VDD") (pinfunction "VDD_VDD") (pintype "power_in"))
      (node (ref "LED46") (pin "VDD") (pinfunction "VDD_VDD") (pintype "power_in"))
      (node (ref "LED47") (pin "VDD") (pinfunction "VDD_VDD") (pintype "power_in"))
      (node (ref "LED48") (pin "VDD") (pinfunction "VDD_VDD") (pintype "power_in"))
      (node (ref "LED49") (pin "VDD") (pinfunction "VDD_VDD") (pintype "power_in"))
      (node (ref "LED5") (pin "VDD") (pinfunction "VDD_VDD") (pintype "power_in"))
      (node (ref "LED50") (pin "VDD") (pinfunction "VDD_VDD") (pintype "power_in"))
      (node (ref "LED51") (pin "VDD") (pinfunction "VDD_VDD") (pintype "power_in"))
      (node (ref "LED52") (pin "VDD") (pinfunction "VDD_VDD") (pintype "power_in"))
      (node (ref "LED53") (pin "VDD") (pinfunction "VDD_VDD") (pintype "power_in"))
      (node (ref "LED54") (pin "VDD") (pinfunction "VDD_VDD") (pintype "power_in"))
      (node (ref "LED55") (pin "VDD") (pinfunction "VDD_VDD") (pintype "power_in"))
      (node (ref "LED56") (pin "VDD") (pinfunction "VDD_VDD") (pintype "power_in"))
      (node (ref "LED57") (pin "VDD") (pinfunction "VDD_VDD") (pintype "power_in"))
      (node (ref "LED58") (pin "VDD") (pinfunction "VDD_VDD") (pintype "power_in"))
      (node (ref "LED59") (pin "VDD") (pinfunction "VDD_VDD") (pintype "power_in"))
      (node (ref "LED6") (pin "VDD") (pinfunction "VDD_VDD") (pintype "power_in"))
      (node (ref "LED60") (pin "VDD") (pinfunction "VDD_VDD") (pintype "power_in"))
      (node (ref "LED61") (pin "VDD") (pinfunction "VDD_VDD") (pintype "power_in"))
      (node (ref "LED62") (pin "VDD") (pinfunction "VDD_VDD") (pintype "power_in"))
      (node (ref "LED63") (pin "VDD") (pinfunction "VDD_VDD") (pintype "power_in"))
      (node (ref "LED64") (pin "VDD") (pinfunction "VDD_VDD") (pintype "power_in"))
      (node (ref "LED65") (pin "VDD") (pinfunction "VDD_VDD") (pintype "power_in"))
      (node (ref "LED66") (pin "VDD") (pinfunction "VDD_VDD") (pintype "power_in"))
      (node (ref "LED67") (pin "VDD") (pinfunction "VDD_VDD") (pintype "power_in"))
      (node (ref "LED68") (pin "VDD") (pinfunction "VDD_VDD") (pintype "power_in"))
      (node (ref "LED69") (pin "VDD") (pinfunction "VDD_VDD") (pintype "power_in"))
      (node (ref "LED7") (pin "VDD") (pinfunction "VDD_VDD") (pintype "power_in"))
      (node (ref "LED70") (pin "VDD") (pinfunction "VDD_VDD") (pintype "power_in"))
      (node (ref "LED71") (pin "VDD") (pinfunction "VDD_VDD") (pintype "power_in"))
      (node (ref "LED72") (pin "VDD") (pinfunction "VDD_VDD") (pintype "power_in"))
      (node (ref "LED73") (pin "VDD") (pinfunction "VDD_VDD") (pintype "power_in"))
      (node (ref "LED74") (pin "VDD") (pinfunction "VDD_VDD") (pintype "power_in"))
      (node (ref "LED75") (pin "VDD") (pinfunction "VDD_VDD") (pintype "power_in"))
      (node (ref "LED76") (pin "VDD") (pinfunction "VDD_VDD") (pintype "power_in"))
      (node (ref "LED77") (pin "VDD") (pinfunction "VDD_VDD") (pintype "power_in"))
      (node (ref "LED78") (pin "VDD") (pinfunction "VDD_VDD") (pintype "power_in"))
      (node (ref "LED79") (pin "VDD") (pinfunction "VDD_VDD") (pintype "power_in"))
      (node (ref "LED8") (pin "VDD") (pinfunction "VDD_VDD") (pintype "power_in"))
      (node (ref "LED80") (pin "VDD") (pinfunction "VDD_VDD") (pintype "power_in"))
      (node (ref "LED81") (pin "VDD") (pinfunction "VDD_VDD") (pintype "power_in"))
      (node (ref "LED82") (pin "VDD") (pinfunction "VDD_VDD") (pintype "power_in"))
      (node (ref "LED83") (pin "VDD") (pinfunction "VDD_VDD") (pintype "power_in"))
      (node (ref "LED84") (pin "VDD") (pinfunction "VDD_VDD") (pintype "power_in"))
      (node (ref "LED85") (pin "VDD") (pinfunction "VDD_VDD") (pintype "power_in"))
      (node (ref "LED86") (pin "VDD") (pinfunction "VDD_VDD") (pintype "power_in"))
      (node (ref "LED87") (pin "VDD") (pinfunction "VDD_VDD") (pintype "power_in"))
      (node (ref "LED88") (pin "VDD") (pinfunction "VDD_VDD") (pintype "power_in"))
      (node (ref "LED89") (pin "VDD") (pinfunction "VDD_VDD") (pintype "power_in"))
      (node (ref "LED9") (pin "VDD") (pinfunction "VDD_VDD") (pintype "power_in"))
      (node (ref "LED90") (pin "VDD") (pinfunction "VDD_VDD") (pintype "power_in"))
      (node (ref "LED91") (pin "VDD") (pinfunction "VDD_VDD") (pintype "power_in"))
      (node (ref "LED92") (pin "VDD") (pinfunction "VDD_VDD") (pintype "power_in"))
      (node (ref "LED93") (pin "VDD") (pinfunction "VDD_VDD") (pintype "power_in"))
      (node (ref "LED94") (pin "VDD") (pinfunction "VDD_VDD") (pintype "power_in"))
      (node (ref "LED95") (pin "VDD") (pinfunction "VDD_VDD") (pintype "power_in"))
      (node (ref "LED96") (pin "VDD") (pinfunction "VDD_VDD") (pintype "power_in"))
      (node (ref "LED97") (pin "VDD") (pinfunction "VDD_VDD") (pintype "power_in"))
      (node (ref "LED98") (pin "VDD") (pinfunction "VDD_VDD") (pintype "power_in"))
      (node (ref "LED99") (pin "VDD") (pinfunction "VDD_VDD") (pintype "power_in"))
    )
    (net (code "3") (name "DATA") (class "Default")
      (node (ref "IC1") (pin "3") (pinfunction "A_3") (pintype "bidirectional"))
      (node (ref "SJ1") (pin "2") (pinfunction "2_2") (pintype "passive"))
    )
    (net (code "4") (name "DI_FIRST") (class "Default")
      (node (ref "IC1") (pin "4") (pinfunction "B_4") (pintype "bidirectional"))
      (node (ref "J1") (pin "2") (pinfunction "2_2") (pintype "passive"))
      (node (ref "LED1") (pin "DI") (pinfunction "DI_DI") (pintype "input"))
    )
    (net (code "5") (name "DO_LAST") (class "Default")
      (node (ref "J2") (pin "2") (pinfunction "2_2") (pintype "passive"))
      (node (ref "LED144") (pin "DO") (pinfunction "DO_DO") (pintype "output"))
    )
    (net (code "6") (name "DO_MID") (class "Default")
      (node (ref "LED72") (pin "DO") (pinfunction "DO_DO") (pintype "output"))
      (node (ref "LED73") (pin "DI") (pinfunction "DI_DI") (pintype "input"))
    )
    (net (code "7") (name "GND") (class "Default")
      (node (ref "C1") (pin "2") (pinfunction "2_2") (pintype "passive"))
      (node (ref "C2") (pin "2") (pinfunction "2_2") (pintype "passive"))
      (node (ref "C3") (pin "2") (pinfunction "2_2") (pintype "passive"))
      (node (ref "C4") (pin "2") (pinfunction "2_2") (pintype "passive"))
      (node (ref "IC1") (pin "2") (pinfunction "GND_2") (pintype "power_in"))
      (node (ref "J1") (pin "1") (pinfunction "1_1") (pintype "passive"))
      (node (ref "J2") (pin "1") (pinfunction "1_1") (pintype "passive"))
      (node (ref "J3") (pin "13") (pinfunction "13_13") (pintype "passive"))
      (node (ref "J3") (pin "20") (pinfunction "20_20") (pintype "passive"))
      (node (ref "J3") (pin "5") (pinfunction "5_5") (pintype "passive"))
      (node (ref "J4") (pin "10") (pinfunction "10_10") (pintype "passive"))
      (node (ref "J4") (pin "15") (pinfunction "15_15") (pintype "passive"))
      (node (ref "J4") (pin "17") (pinfunction "17_17") (pintype "passive"))
      (node (ref "J4") (pin "3") (pinfunction "3_3") (pintype "passive"))
      (node (ref "J4") (pin "7") (pinfunction "7_7") (pintype "passive"))
      (node (ref "LED1") (pin "GND") (pinfunction "GND_GND") (pintype "power_in"))
      (node (ref "LED10") (pin "GND") (pinfunction "GND_GND") (pintype "power_in"))
      (node (ref "LED100") (pin "GND") (pinfunction "GND_GND") (pintype "power_in"))
      (node (ref "LED101") (pin "GND") (pinfunction "GND_GND") (pintype "power_in"))
      (node (ref "LED102") (pin "GND") (pinfunction "GND_GND") (pintype "power_in"))
      (node (ref "LED103") (pin "GND") (pinfunction "GND_GND") (pintype "power_in"))
      (node (ref "LED104") (pin "GND") (pinfunction "GND_GND") (pintype "power_in"))
      (node (ref "LED105") (pin "GND") (pinfunction "GND_GND") (pintype "power_in"))
      (node (ref "LED106") (pin "GND") (pinfunction "GND_GND") (pintype "power_in"))
      (node (ref "LED107") (pin "GND") (pinfunction "GND_GND") (pintype "power_in"))
      (node (ref "LED108") (pin "GND") (pinfunction "GND_GND") (pintype "power_in"))
      (node (ref "LED109") (pin "GND") (pinfunction "GND_GND") (pintype "power_in"))
      (node (ref "LED11") (pin "GND") (pinfunction "GND_GND") (pintype "power_in"))
      (node (ref "LED110") (pin "GND") (pinfunction "GND_GND") (pintype "power_in"))
      (node (ref "LED111") (pin "GND") (pinfunction "GND_GND") (pintype "power_in"))
      (node (ref "LED112") (pin "GND") (pinfunction "GND_GND") (pintype "power_in"))
      (node (ref "LED113") (pin "GND") (pinfunction "GND_GND") (pintype "power_in"))
      (node (ref "LED114") (pin "GND") (pinfunction "GND_GND") (pintype "power_in"))
      (node (ref "LED115") (pin "GND") (pinfunction "GND_GND") (pintype "power_in"))
      (node (ref "LED116") (pin "GND") (pinfunction "GND_GND") (pintype "power_in"))
      (node (ref "LED117") (pin "GND") (pinfunction "GND_GND") (pintype "power_in"))
      (node (ref "LED118") (pin "GND") (pinfunction "GND_GND") (pintype "power_in"))
      (node (ref "LED119") (pin "GND") (pinfunction "GND_GND") (pintype "power_in"))
      (node (ref "LED12") (pin "GND") (pinfunction "GND_GND") (pintype "power_in"))
      (node (ref "LED120") (pin "GND") (pinfunction "GND_GND") (pintype "power_in"))
      (node (ref "LED121") (pin "GND") (pinfunction "GND_GND") (pintype "power_in"))
      (node (ref "LED122") (pin "GND") (pinfunction "GND_GND") (pintype "power_in"))
      (node (ref "LED123") (pin "GND") (pinfunction "GND_GND") (pintype "power_in"))
      (node (ref "LED124") (pin "GND") (pinfunction "GND_GND") (pintype "power_in"))
      (node (ref "LED125") (pin "GND") (pinfunction "GND_GND") (pintype "power_in"))
      (node (ref "LED126") (pin "GND") (pinfunction "GND_GND") (pintype "power_in"))
      (node (ref "LED127") (pin "GND") (pinfunction "GND_GND") (pintype "power_in"))
      (node (ref "LED128") (pin "GND") (pinfunction "GND_GND") (pintype "power_in"))
      (node (ref "LED129") (pin "GND") (pinfunction "GND_GND") (pintype "power_in"))
      (node (ref "LED13") (pin "GND") (pinfunction "GND_GND") (pintype "power_in"))
      (node (ref "LED130") (pin "GND") (pinfunction "GND_GND") (pintype "power_in"))
      (node (ref "LED131") (pin "GND") (pinfunction "GND_GND") (pintype "power_in"))
      (node (ref "LED132") (pin "GND") (pinfunction "GND_GND") (pintype "power_in"))
      (node (ref "LED133") (pin "GND") (pinfunction "GND_GND") (pintype "power_in"))
      (node (ref "LED134") (pin "GND") (pinfunction "GND_GND") (pintype "power_in"))
      (node (ref "LED135") (pin "GND") (pinfunction "GND_GND") (pintype "power_in"))
      (node (ref "LED136") (pin "GND") (pinfunction "GND_GND") (pintype "power_in"))
      (node (ref "LED137") (pin "GND") (pinfunction "GND_GND") (pintype "power_in"))
      (node (ref "LED138") (pin "GND") (pinfunction "GND_GND") (pintype "power_in"))
      (node (ref "LED139") (pin "GND") (pinfunction "GND_GND") (pintype "power_in"))
      (node (ref "LED14") (pin "GND") (pinfunction "GND_GND") (pintype "power_in"))
      (node (ref "LED140") (pin "GND") (pinfunction "GND_GND") (pintype "power_in"))
      (node (ref "LED141") (pin "GND") (pinfunction "GND_GND") (pintype "power_in"))
      (node (ref "LED142") (pin "GND") (pinfunction "GND_GND") (pintype "power_in"))
      (node (ref "LED143") (pin "GND") (pinfunction "GND_GND") (pintype "power_in"))
      (node (ref "LED144") (pin "GND") (pinfunction "GND_GND") (pintype "power_in"))
      (node (ref "LED15") (pin "GND") (pinfunction "GND_GND") (pintype "power_in"))
      (node (ref "LED16") (pin "GND") (pinfunction "GND_GND") (pintype "power_in"))
      (node (ref "LED17") (pin "GND") (pinfunction "GND_GND") (pintype "power_in"))
      (node (ref "LED18") (pin "GND") (pinfunction "GND_GND") (pintype "power_in"))
      (node (ref "LED19") (pin "GND") (pinfunction "GND_GND") (pintype "power_in"))
      (node (ref "LED2") (pin "GND") (pinfunction "GND_GND") (pintype "power_in"))
      (node (ref "LED20") (pin "GND") (pinfunction "GND_GND") (pintype "power_in"))
      (node (ref "LED21") (pin "GND") (pinfunction "GND_GND") (pintype "power_in"))
      (node (ref "LED22") (pin "GND") (pinfunction "GND_GND") (pintype "power_in"))
      (node (ref "LED23") (pin "GND") (pinfunction "GND_GND") (pintype "power_in"))
      (node (ref "LED24") (pin "GND") (pinfunction "GND_GND") (pintype "power_in"))
      (node (ref "LED25") (pin "GND") (pinfunction "GND_GND") (pintype "power_in"))
      (node (ref "LED26") (pin "GND") (pinfunction "GND_GND") (pintype "power_in"))
      (node (ref "LED27") (pin "GND") (pinfunction "GND_GND") (pintype "power_in"))
      (node (ref "LED28") (pin "GND") (pinfunction "GND_GND") (pintype "power_in"))
      (node (ref "LED29") (pin "GND") (pinfunction "GND_GND") (pintype "power_in"))
      (node (ref "LED3") (pin "GND") (pinfunction "GND_GND") (pintype "power_in"))
      (node (ref "LED30") (pin "GND") (pinfunction "GND_GND") (pintype "power_in"))
      (node (ref "LED31") (pin "GND") (pinfunction "GND_GND") (pintype "power_in"))
      (node (ref "LED32") (pin "GND") (pinfunction "GND_GND") (pintype "power_in"))
      (node (ref "LED33") (pin "GND") (pinfunction "GND_GND") (pintype "power_in"))
      (node (ref "LED34") (pin "GND") (pinfunction "GND_GND") (pintype "power_in"))
      (node (ref "LED35") (pin "GND") (pinfunction "GND_GND") (pintype "power_in"))
      (node (ref "LED36") (pin "GND") (pinfunction "GND_GND") (pintype "power_in"))
      (node (ref "LED37") (pin "GND") (pinfunction "GND_GND") (pintype "power_in"))
      (node (ref "LED38") (pin "GND") (pinfunction "GND_GND") (pintype "power_in"))
      (node (ref "LED39") (pin "GND") (pinfunction "GND_GND") (pintype "power_in"))
      (node (ref "LED4") (pin "GND") (pinfunction "GND_GND") (pintype "power_in"))
      (node (ref "LED40") (pin "GND") (pinfunction "GND_GND") (pintype "power_in"))
      (node (ref "LED41") (pin "GND") (pinfunction "GND_GND") (pintype "power_in"))
      (node (ref "LED42") (pin "GND") (pinfunction "GND_GND") (pintype "power_in"))
      (node (ref "LED43") (pin "GND") (pinfunction "GND_GND") (pintype "power_in"))
      (node (ref "LED44") (pin "GND") (pinfunction "GND_GND") (pintype "power_in"))
      (node (ref "LED45") (pin "GND") (pinfunction "GND_GND") (pintype "power_in"))
      (node (ref "LED46") (pin "GND") (pinfunction "GND_GND") (pintype "power_in"))
      (node (ref "LED47") (pin "GND") (pinfunction "GND_GND") (pintype "power_in"))
      (node (ref "LED48") (pin "GND") (pinfunction "GND_GND") (pintype "power_in"))
      (node (ref "LED49") (pin "GND") (pinfunction "GND_GND") (pintype "power_in"))
      (node (ref "LED5") (pin "GND") (pinfunction "GND_GND") (pintype "power_in"))
      (node (ref "LED50") (pin "GND") (pinfunction "GND_GND") (pintype "power_in"))
      (node (ref "LED51") (pin "GND") (pinfunction "GND_GND") (pintype "power_in"))
      (node (ref "LED52") (pin "GND") (pinfunction "GND_GND") (pintype "power_in"))
      (node (ref "LED53") (pin "GND") (pinfunction "GND_GND") (pintype "power_in"))
      (node (ref "LED54") (pin "GND") (pinfunction "GND_GND") (pintype "power_in"))
      (node (ref "LED55") (pin "GND") (pinfunction "GND_GND") (pintype "power_in"))
      (node (ref "LED56") (pin "GND") (pinfunction "GND_GND") (pintype "power_in"))
      (node (ref "LED57") (pin "GND") (pinfunction "GND_GND") (pintype "power_in"))
      (node (ref "LED58") (pin "GND") (pinfunction "GND_GND") (pintype "power_in"))
      (node (ref "LED59") (pin "GND") (pinfunction "GND_GND") (pintype "power_in"))
      (node (ref "LED6") (pin "GND") (pinfunction "GND_GND") (pintype "power_in"))
      (node (ref "LED60") (pin "GND") (pinfunction "GND_GND") (pintype "power_in"))
      (node (ref "LED61") (pin "GND") (pinfunction "GND_GND") (pintype "power_in"))
      (node (ref "LED62") (pin "GND") (pinfunction "GND_GND") (pintype "power_in"))
      (node (ref "LED63") (pin "GND") (pinfunction "GND_GND") (pintype "power_in"))
      (node (ref "LED64") (pin "GND") (pinfunction "GND_GND") (pintype "power_in"))
      (node (ref "LED65") (pin "GND") (pinfunction "GND_GND") (pintype "power_in"))
      (node (ref "LED66") (pin "GND") (pinfunction "GND_GND") (pintype "power_in"))
      (node (ref "LED67") (pin "GND") (pinfunction "GND_GND") (pintype "power_in"))
      (node (ref "LED68") (pin "GND") (pinfunction "GND_GND") (pintype "power_in"))
      (node (ref "LED69") (pin "GND") (pinfunction "GND_GND") (pintype "power_in"))
      (node (ref "LED7") (pin "GND") (pinfunction "GND_GND") (pintype "power_in"))
      (node (ref "LED70") (pin "GND") (pinfunction "GND_GND") (pintype "power_in"))
      (node (ref "LED71") (pin "GND") (pinfunction "GND_GND") (pintype "power_in"))
      (node (ref "LED72") (pin "GND") (pinfunction "GND_GND") (pintype "power_in"))
      (node (ref "LED73") (pin "GND") (pinfunction "GND_GND") (pintype "power_in"))
      (node (ref "LED74") (pin "GND") (pinfunction "GND_GND") (pintype "power_in"))
      (node (ref "LED75") (pin "GND") (pinfunction "GND_GND") (pintype "power_in"))
      (node (ref "LED76") (pin "GND") (pinfunction "GND_GND") (pintype "power_in"))
      (node (ref "LED77") (pin "GND") (pinfunction "GND_GND") (pintype "power_in"))
      (node (ref "LED78") (pin "GND") (pinfunction "GND_GND") (pintype "power_in"))
      (node (ref "LED79") (pin "GND") (pinfunction "GND_GND") (pintype "power_in"))
      (node (ref "LED8") (pin "GND") (pinfunction "GND_GND") (pintype "power_in"))
      (node (ref "LED80") (pin "GND") (pinfunction "GND_GND") (pintype "power_in"))
      (node (ref "LED81") (pin "GND") (pinfunction "GND_GND") (pintype "power_in"))
      (node (ref "LED82") (pin "GND") (pinfunction "GND_GND") (pintype "power_in"))
      (node (ref "LED83") (pin "GND") (pinfunction "GND_GND") (pintype "power_in"))
      (node (ref "LED84") (pin "GND") (pinfunction "GND_GND") (pintype "power_in"))
      (node (ref "LED85") (pin "GND") (pinfunction "GND_GND") (pintype "power_in"))
      (node (ref "LED86") (pin "GND") (pinfunction "GND_GND") (pintype "power_in"))
      (node (ref "LED87") (pin "GND") (pinfunction "GND_GND") (pintype "power_in"))
      (node (ref "LED88") (pin "GND") (pinfunction "GND_GND") (pintype "power_in"))
      (node (ref "LED89") (pin "GND") (pinfunction "GND_GND") (pintype "power_in"))
      (node (ref "LED9") (pin "GND") (pinfunction "GND_GND") (pintype "power_in"))
      (node (ref "LED90") (pin "GND") (pinfunction "GND_GND") (pintype "power_in"))
      (node (ref "LED91") (pin "GND") (pinfunction "GND_GND") (pintype "power_in"))
      (node (ref "LED92") (pin "GND") (pinfunction "GND_GND") (pintype "power_in"))
      (node (ref "LED93") (pin "GND") (pinfunction "GND_GND") (pintype "power_in"))
      (node (ref "LED94") (pin "GND") (pinfunction "GND_GND") (pintype "power_in"))
      (node (ref "LED95") (pin "GND") (pinfunction "GND_GND") (pintype "power_in"))
      (node (ref "LED96") (pin "GND") (pinfunction "GND_GND") (pintype "power_in"))
      (node (ref "LED97") (pin "GND") (pinfunction "GND_GND") (pintype "power_in"))
      (node (ref "LED98") (pin "GND") (pinfunction "GND_GND") (pintype "power_in"))
      (node (ref "LED99") (pin "GND") (pinfunction "GND_GND") (pintype "power_in"))
    )
    (net (code "8") (name "GPIO0") (class "Default")
      (node (ref "J3") (pin "14") (pinfunction "14_14") (pintype "passive"))
    )
    (net (code "9") (name "GPIO1") (class "Default")
      (node (ref "J4") (pin "14") (pinfunction "14_14") (pintype "passive"))
    )
    (net (code "10") (name "GPIO2") (class "Default")
      (node (ref "J3") (pin "2") (pinfunction "2_2") (pintype "passive"))
    )
    (net (code "11") (name "GPIO3") (class "Default")
      (node (ref "J3") (pin "3") (pinfunction "3_3") (pintype "passive"))
    )
    (net (code "12") (name "GPIO4") (class "Default")
      (node (ref "J3") (pin "4") (pinfunction "4_4") (pintype "passive"))
    )
    (net (code "13") (name "GPIO5") (class "Default")
      (node (ref "J3") (pin "15") (pinfunction "15_15") (pintype "passive"))
    )
    (net (code "14") (name "GPIO6") (class "Default")
      (node (ref "J3") (pin "16") (pinfunction "16_16") (pintype "passive"))
    )
    (net (code "15") (name "GPIO7") (class "Default")
      (node (ref "J4") (pin "13") (pinfunction "13_13") (pintype "passive"))
    )
    (net (code "16") (name "GPIO8") (class "Default")
      (node (ref "J4") (pin "12") (pinfunction "12_12") (pintype "passive"))
    )
    (net (code "17") (name "GPIO9") (class "Default")
      (node (ref "J3") (pin "11") (pinfunction "11_11") (pintype "passive"))
    )
    (net (code "18") (name "GPIO10") (class "Default")
      (node (ref "J3") (pin "10") (pinfunction "10_10") (pintype "passive"))
      (node (ref "SJ1") (pin "3") (pinfunction "3_3") (pintype "passive"))
    )
    (net (code "19") (name "GPIO11") (class "Default")
      (node (ref "J3") (pin "12") (pinfunction "12_12") (pintype "passive"))
    )
    (net (code "20") (name "GPIO12") (class "Default")
      (node (ref "J4") (pin "16") (pinfunction "16_16") (pintype "passive"))
    )
    (net (code "21") (name "GPIO13") (class "Default")
      (node (ref "J3") (pin "17") (pinfunction "17_17") (pintype "passive"))
    )
    (net (code "22") (name "GPIO14") (class "Default")
      (node (ref "J4") (pin "4") (pinfunction "4_4") (pintype "passive"))
    )
    (net (code "23") (name "GPIO15") (class "Default")
      (node (ref "J4") (pin "5") (pinfunction "5_5") (pintype "passive"))
    )
    (net (code "24") (name "GPIO16") (class "Default")
      (node (ref "J4") (pin "18") (pinfunction "18_18") (pintype "passive"))
    )
    (net (code "25") (name "GPIO17") (class "Default")
      (node (ref "J3") (pin "6") (pinfunction "6_6") (pintype "passive"))
    )
    (net (code "26") (name "GPIO18") (class "Default")
      (node (ref "J4") (pin "6") (pinfunction "6_6") (pintype "passive"))
      (node (ref "SJ1") (pin "4") (pinfunction "4_4") (pintype "passive"))
    )
    (net (code "27") (name "GPIO19") (class "Default")
      (node (ref "J3") (pin "18") (pinfunction "18_18") (pintype "passive"))
    )
    (net (code "28") (name "GPIO20") (class "Default")
      (node (ref "J4") (pin "19") (pinfunction "19_19") (pintype "passive"))
    )
    (net (code "29") (name "GPIO21") (class "Default")
      (node (ref "J4") (pin "20") (pinfunction "20_20") (pintype "passive"))
      (node (ref "SJ1") (pin "1") (pinfunction "1_1") (pintype "passive"))
    )
    (net (code "30") (name "GPIO22") (class "Default")
      (node (ref "J3") (pin "8") (pinfunction "8_8") (pintype "passive"))
    )
    (net (code "31") (name "GPIO23") (class "Default")
      (node (ref "J4") (pin "8") (pinfunction "8_8") (pintype "passive"))
    )
    (net (code "32") (name "GPIO24") (class "Default")
      (node (ref "J4") (pin "9") (pinfunction "9_9") (pintype "passive"))
    )
    (net (code "33") (name "GPIO25") (class "Default")
      (node (ref "J4") (pin "11") (pinfunction "11_11") (pintype "passive"))
    )
    (net (code "34") (name "GPIO26") (class "Default")
      (node (ref "J3") (pin "19") (pinfunction "19_19") (pintype "passive"))
    )
    (net (code "35") (name "GPIO27") (class "Default")
      (node (ref "J3") (pin "7") (pinfunction "7_7") (pintype "passive"))
    )
    (net (code "36") (name "Net-(IC1-OE)") (class "Default")
      (node (ref "IC1") (pin "5") (pinfunction "OE_5") (pintype "input"))
      (node (ref "R1") (pin "2") (pinfunction "2_2") (pintype "passive"))
    )
    (net (code "37") (name "Net-(LED1-PadDO)") (class "Default")
      (node (ref "LED1") (pin "DO") (pinfunction "DO_DO") (pintype "output"))
      (node (ref "LED2") (pin "DI") (pinfunction "DI_DI") (pintype "input"))
    )
    (net (code "38") (name "Net-(LED2-PadDO)") (class "Default")
      (node (ref "LED2") (pin "DO") (pinfunction "DO_DO") (pintype "output"))
      (node (ref "LED3") (pin "DI") (pinfunction "DI_DI") (pintype "input"))
    )
    (net (code "39") (name "Net-(LED3-PadDO)") (class "Default")
      (node (ref "LED3") (pin "DO") (pinfunction "DO_DO") (pintype "output"))
      (node (ref "LED4") (pin "DI") (pinfunction "DI_DI") (pintype "input"))
    )
    (net (code "40") (name "Net-(LED4-PadDO)") (class "Default")
      (node (ref "LED4") (pin "DO") (pinfunction "DO_DO") (pintype "output"))
      (node (ref "LED5") (pin "DI") (pinfunction "DI_DI") (pintype "input"))
    )
    (net (code "41") (name "Net-(LED5-PadDO)") (class "Default")
      (node (ref "LED5") (pin "DO") (pinfunction "DO_DO") (pintype "output"))
      (node (ref "LED6") (pin "DI") (pinfunction "DI_DI") (pintype "input"))
    )
    (net (code "42") (name "Net-(LED6-PadDO)") (class "Default")
      (node (ref "LED6") (pin "DO") (pinfunction "DO_DO") (pintype "output"))
      (node (ref "LED7") (pin "DI") (pinfunction "DI_DI") (pintype "input"))
    )
    (net (code "43") (name "Net-(LED7-PadDO)") (class "Default")
      (node (ref "LED7") (pin "DO") (pinfunction "DO_DO") (pintype "output"))
      (node (ref "LED8") (pin "DI") (pinfunction "DI_DI") (pintype "input"))
    )
    (net (code "44") (name "Net-(LED8-PadDO)") (class "Default")
      (node (ref "LED8") (pin "DO") (pinfunction "DO_DO") (pintype "output"))
      (node (ref "LED9") (pin "DI") (pinfunction "DI_DI") (pintype "input"))
    )
    (net (code "45") (name "Net-(LED10-PadDI)") (class "Default")
      (node (ref "LED10") (pin "DI") (pinfunction "DI_DI") (pintype "input"))
      (node (ref "LED9") (pin "DO") (pinfunction "DO_DO") (pintype "output"))
    )
    (net (code "46") (name "Net-(LED10-PadDO)") (class "Default")
      (node (ref "LED10") (pin "DO") (pinfunction "DO_DO") (pintype "output"))
      (node (ref "LED11") (pin "DI") (pinfunction "DI_DI") (pintype "input"))
    )
    (net (code "47") (name "Net-(LED11-PadDO)") (class "Default")
      (node (ref "LED11") (pin "DO") (pinfunction "DO_DO") (pintype "output"))
      (node (ref "LED12") (pin "DI") (pinfunction "DI_DI") (pintype "input"))
    )
    (net (code "48") (name "Net-(LED12-PadDO)") (class "Default")
      (node (ref "LED12") (pin "DO") (pinfunction "DO_DO") (pintype "output"))
      (node (ref "LED13") (pin "DI") (pinfunction "DI_DI") (pintype "input"))
    )
    (net (code "49") (name "Net-(LED13-PadDO)") (class "Default")
      (node (ref "LED13") (pin "DO") (pinfunction "DO_DO") (pintype "output"))
      (node (ref "LED14") (pin "DI") (pinfunction "DI_DI") (pintype "input"))
    )
    (net (code "50") (name "Net-(LED14-PadDO)") (class "Default")
      (node (ref "LED14") (pin "DO") (pinfunction "DO_DO") (pintype "output"))
      (node (ref "LED15") (pin "DI") (pinfunction "DI_DI") (pintype "input"))
    )
    (net (code "51") (name "Net-(LED15-PadDO)") (class "Default")
      (node (ref "LED15") (pin "DO") (pinfunction "DO_DO") (pintype "output"))
      (node (ref "LED16") (pin "DI") (pinfunction "DI_DI") (pintype "input"))
    )
    (net (code "52") (name "Net-(LED16-PadDO)") (class "Default")
      (node (ref "LED16") (pin "DO") (pinfunction "DO_DO") (pintype "output"))
      (node (ref "LED17") (pin "DI") (pinfunction "DI_DI") (pintype "input"))
    )
    (net (code "53") (name "Net-(LED17-PadDO)") (class "Default")
      (node (ref "LED17") (pin "DO") (pinfunction "DO_DO") (pintype "output"))
      (node (ref "LED18") (pin "DI") (pinfunction "DI_DI") (pintype "input"))
    )
    (net (code "54") (name "Net-(LED18-PadDO)") (class "Default")
      (node (ref "LED18") (pin "DO") (pinfunction "DO_DO") (pintype "output"))
      (node (ref "LED19") (pin "DI") (pinfunction "DI_DI") (pintype "input"))
    )
    (net (code "55") (name "Net-(LED19-PadDO)") (class "Default")
      (node (ref "LED19") (pin "DO") (pinfunction "DO_DO") (pintype "output"))
      (node (ref "LED20") (pin "DI") (pinfunction "DI_DI") (pintype "input"))
    )
    (net (code "56") (name "Net-(LED20-PadDO)") (class "Default")
      (node (ref "LED20") (pin "DO") (pinfunction "DO_DO") (pintype "output"))
      (node (ref "LED21") (pin "DI") (pinfunction "DI_DI") (pintype "input"))
    )
    (net (code "57") (name "Net-(LED21-PadDO)") (class "Default")
      (node (ref "LED21") (pin "DO") (pinfunction "DO_DO") (pintype "output"))
      (node (ref "LED22") (pin "DI") (pinfunction "DI_DI") (pintype "input"))
    )
    (net (code "58") (name "Net-(LED22-PadDO)") (class "Default")
      (node (ref "LED22") (pin "DO") (pinfunction "DO_DO") (pintype "output"))
      (node (ref "LED23") (pin "DI") (pinfunction "DI_DI") (pintype "input"))
    )
    (net (code "59") (name "Net-(LED23-PadDO)") (class "Default")
      (node (ref "LED23") (pin "DO") (pinfunction "DO_DO") (pintype "output"))
      (node (ref "LED24") (pin "DI") (pinfunction "DI_DI") (pintype "input"))
    )
    (net (code "60") (name "Net-(LED24-PadDO)") (class "Default")
      (node (ref "LED24") (pin "DO") (pinfunction "DO_DO") (pintype "output"))
      (node (ref "LED25") (pin "DI") (pinfunction "DI_DI") (pintype "input"))
    )
    (net (code "61") (name "Net-(LED25-PadDO)") (class "Default")
      (node (ref "LED25") (pin "DO") (pinfunction "DO_DO") (pintype "output"))
      (node (ref "LED26") (pin "DI") (pinfunction "DI_DI") (pintype "input"))
    )
    (net (code "62") (name "Net-(LED26-PadDO)") (class "Default")
      (node (ref "LED26") (pin "DO") (pinfunction "DO_DO") (pintype "output"))
      (node (ref "LED27") (pin "DI") (pinfunction "DI_DI") (pintype "input"))
    )
    (net (code "63") (name "Net-(LED27-PadDO)") (class "Default")
      (node (ref "LED27") (pin "DO") (pinfunction "DO_DO") (pintype "output"))
      (node (ref "LED28") (pin "DI") (pinfunction "DI_DI") (pintype "input"))
    )
    (net (code "64") (name "Net-(LED28-PadDO)") (class "Default")
      (node (ref "LED28") (pin "DO") (pinfunction "DO_DO") (pintype "output"))
      (node (ref "LED29") (pin "DI") (pinfunction "DI_DI") (pintype "input"))
    )
    (net (code "65") (name "Net-(LED29-PadDO)") (class "Default")
      (node (ref "LED29") (pin "DO") (pinfunction "DO_DO") (pintype "output"))
      (node (ref "LED30") (pin "DI") (pinfunction "DI_DI") (pintype "input"))
    )
    (net (code "66") (name "Net-(LED30-PadDO)") (class "Default")
      (node (ref "LED30") (pin "DO") (pinfunction "DO_DO") (pintype "output"))
      (node (ref "LED31") (pin "DI") (pinfunction "DI_DI") (pintype "input"))
    )
    (net (code "67") (name "Net-(LED31-PadDO)") (class "Default")
      (node (ref "LED31") (pin "DO") (pinfunction "DO_DO") (pintype "output"))
      (node (ref "LED32") (pin "DI") (pinfunction "DI_DI") (pintype "input"))
    )
    (net (code "68") (name "Net-(LED32-PadDO)") (class "Default")
      (node (ref "LED32") (pin "DO") (pinfunction "DO_DO") (pintype "output"))
      (node (ref "LED33") (pin "DI") (pinfunction "DI_DI") (pintype "input"))
    )
    (net (code "69") (name "Net-(LED33-PadDO)") (class "Default")
      (node (ref "LED33") (pin "DO") (pinfunction "DO_DO") (pintype "output"))
      (node (ref "LED34") (pin "DI") (pinfunction "DI_DI") (pintype "input"))
    )
    (net (code "70") (name "Net-(LED34-PadDO)") (class "Default")
      (node (ref "LED34") (pin "DO") (pinfunction "DO_DO") (pintype "output"))
      (node (ref "LED35") (pin "DI") (pinfunction "DI_DI") (pintype "input"))
    )
    (net (code "71") (name "Net-(LED35-PadDO)") (class "Default")
      (node (ref "LED35") (pin "DO") (pinfunction "DO_DO") (pintype "output"))
      (node (ref "LED36") (pin "DI") (pinfunction "DI_DI") (pintype "input"))
    )
    (net (code "72") (name "Net-(LED36-PadDO)") (class "Default")
      (node (ref "LED36") (pin "DO") (pinfunction "DO_DO") (pintype "output"))
      (node (ref "LED37") (pin "DI") (pinfunction "DI_DI") (pintype "input"))
    )
    (net (code "73") (name "Net-(LED37-PadDO)") (class "Default")
      (node (ref "LED37") (pin "DO") (pinfunction "DO_DO") (pintype "output"))
      (node (ref "LED38") (pin "DI") (pinfunction "DI_DI") (pintype "input"))
    )
    (net (code "74") (name "Net-(LED38-PadDO)") (class "Default")
      (node (ref "LED38") (pin "DO") (pinfunction "DO_DO") (pintype "output"))
      (node (ref "LED39") (pin "DI") (pinfunction "DI_DI") (pintype "input"))
    )
    (net (code "75") (name "Net-(LED39-PadDO)") (class "Default")
      (node (ref "LED39") (pin "DO") (pinfunction "DO_DO") (pintype "output"))
      (node (ref "LED40") (pin "DI") (pinfunction "DI_DI") (pintype "input"))
    )
    (net (code "76") (name "Net-(LED40-PadDO)") (class "Default")
      (node (ref "LED40") (pin "DO") (pinfunction "DO_DO") (pintype "output"))
      (node (ref "LED41") (pin "DI") (pinfunction "DI_DI") (pintype "input"))
    )
    (net (code "77") (name "Net-(LED41-PadDO)") (class "Default")
      (node (ref "LED41") (pin "DO") (pinfunction "DO_DO") (pintype "output"))
      (node (ref "LED42") (pin "DI") (pinfunction "DI_DI") (pintype "input"))
    )
    (net (code "78") (name "Net-(LED42-PadDO)") (class "Default")
      (node (ref "LED42") (pin "DO") (pinfunction "DO_DO") (pintype "output"))
      (node (ref "LED43") (pin "DI") (pinfunction "DI_DI") (pintype "input"))
    )
    (net (code "79") (name "Net-(LED43-PadDO)") (class "Default")
      (node (ref "LED43") (pin "DO") (pinfunction "DO_DO") (pintype "output"))
      (node (ref "LED44") (pin "DI") (pinfunction "DI_DI") (pintype "input"))
    )
    (net (code "80") (name "Net-(LED44-PadDO)") (class "Default")
      (node (ref "LED44") (pin "DO") (pinfunction "DO_DO") (pintype "output"))
      (node (ref "LED45") (pin "DI") (pinfunction "DI_DI") (pintype "input"))
    )
    (net (code "81") (name "Net-(LED45-PadDO)") (class "Default")
      (node (ref "LED45") (pin "DO") (pinfunction "DO_DO") (pintype "output"))
      (node (ref "LED46") (pin "DI") (pinfunction "DI_DI") (pintype "input"))
    )
    (net (code "82") (name "Net-(LED46-PadDO)") (class "Default")
      (node (ref "LED46") (pin "DO") (pinfunction "DO_DO") (pintype "output"))
      (node (ref "LED47") (pin "DI") (pinfunction "DI_DI") (pintype "input"))
    )
    (net (code "83") (name "Net-(LED47-PadDO)") (class "Default")
      (node (ref "LED47") (pin "DO") (pinfunction "DO_DO") (pintype "output"))
      (node (ref "LED48") (pin "DI") (pinfunction "DI_DI") (pintype "input"))
    )
    (net (code "84") (name "Net-(LED48-PadDO)") (class "Default")
      (node (ref "LED48") (pin "DO") (pinfunction "DO_DO") (pintype "output"))
      (node (ref "LED49") (pin "DI") (pinfunction "DI_DI") (pintype "input"))
    )
    (net (code "85") (name "Net-(LED49-PadDO)") (class "Default")
      (node (ref "LED49") (pin "DO") (pinfunction "DO_DO") (pintype "output"))
      (node (ref "LED50") (pin "DI") (pinfunction "DI_DI") (pintype "input"))
    )
    (net (code "86") (name "Net-(LED50-PadDO)") (class "Default")
      (node (ref "LED50") (pin "DO") (pinfunction "DO_DO") (pintype "output"))
      (node (ref "LED51") (pin "DI") (pinfunction "DI_DI") (pintype "input"))
    )
    (net (code "87") (name "Net-(LED51-PadDO)") (class "Default")
      (node (ref "LED51") (pin "DO") (pinfunction "DO_DO") (pintype "output"))
      (node (ref "LED52") (pin "DI") (pinfunction "DI_DI") (pintype "input"))
    )
    (net (code "88") (name "Net-(LED52-PadDO)") (class "Default")
      (node (ref "LED52") (pin "DO") (pinfunction "DO_DO") (pintype "output"))
      (node (ref "LED53") (pin "DI") (pinfunction "DI_DI") (pintype "input"))
    )
    (net (code "89") (name "Net-(LED53-PadDO)") (class "Default")
      (node (ref "LED53") (pin "DO") (pinfunction "DO_DO") (pintype "output"))
      (node (ref "LED54") (pin "DI") (pinfunction "DI_DI") (pintype "input"))
    )
    (net (code "90") (name "Net-(LED54-PadDO)") (class "Default")
      (node (ref "LED54") (pin "DO") (pinfunction "DO_DO") (pintype "output"))
      (node (ref "LED55") (pin "DI") (pinfunction "DI_DI") (pintype "input"))
    )
    (net (code "91") (name "Net-(LED55-PadDO)") (class "Default")
      (node (ref "LED55") (pin "DO") (pinfunction "DO_DO") (pintype "output"))
      (node (ref "LED56") (pin "DI") (pinfunction "DI_DI") (pintype "input"))
    )
    (net (code "92") (name "Net-(LED56-PadDO)") (class "Default")
      (node (ref "LED56") (pin "DO") (pinfunction "DO_DO") (pintype "output"))
      (node (ref "LED57") (pin "DI") (pinfunction "DI_DI") (pintype "input"))
    )
    (net (code "93") (name "Net-(LED57-PadDO)") (class "Default")
      (node (ref "LED57") (pin "DO") (pinfunction "DO_DO") (pintype "output"))
      (node (ref "LED58") (pin "DI") (pinfunction "DI_DI") (pintype "input"))
    )
    (net (code "94") (name "Net-(LED58-PadDO)") (class "Default")
      (node (ref "LED58") (pin "DO") (pinfunction "DO_DO") (pintype "output"))
      (node (ref "LED59") (pin "DI") (pinfunction "DI_DI") (pintype "input"))
    )
    (net (code "95") (name "Net-(LED59-PadDO)") (class "Default")
      (node (ref "LED59") (pin "DO") (pinfunction "DO_DO") (pintype "output"))
      (node (ref "LED60") (pin "DI") (pinfunction "DI_DI") (pintype "input"))
    )
    (net (code "96") (name "Net-(LED60-PadDO)") (class "Default")
      (node (ref "LED60") (pin "DO") (pinfunction "DO_DO") (pintype "output"))
      (node (ref "LED61") (pin "DI") (pinfunction "DI_DI") (pintype "input"))
    )
    (net (code "97") (name "Net-(LED61-PadDO)") (class "Default")
      (node (ref "LED61") (pin "DO") (pinfunction "DO_DO") (pintype "output"))
      (node (ref "LED62") (pin "DI") (pinfunction "DI_DI") (pintype "input"))
    )
    (net (code "98") (name "Net-(LED62-PadDO)") (class "Default")
      (node (ref "LED62") (pin "DO") (pinfunction "DO_DO") (pintype "output"))
      (node (ref "LED63") (pin "DI") (pinfunction "DI_DI") (pintype "input"))
    )
    (net (code "99") (name "Net-(LED63-PadDO)") (class "Default")
      (node (ref "LED63") (pin "DO") (pinfunction "DO_DO") (pintype "output"))
      (node (ref "LED64") (pin "DI") (pinfunction "DI_DI") (pintype "input"))
    )
    (net (code "100") (name "Net-(LED64-PadDO)") (class "Default")
      (node (ref "LED64") (pin "DO") (pinfunction "DO_DO") (pintype "output"))
      (node (ref "LED65") (pin "DI") (pinfunction "DI_DI") (pintype "input"))
    )
    (net (code "101") (name "Net-(LED65-PadDO)") (class "Default")
      (node (ref "LED65") (pin "DO") (pinfunction "DO_DO") (pintype "output"))
      (node (ref "LED66") (pin "DI") (pinfunction "DI_DI") (pintype "input"))
    )
    (net (code "102") (name "Net-(LED66-PadDO)") (class "Default")
      (node (ref "LED66") (pin "DO") (pinfunction "DO_DO") (pintype "output"))
      (node (ref "LED67") (pin "DI") (pinfunction "DI_DI") (pintype "input"))
    )
    (net (code "103") (name "Net-(LED67-PadDO)") (class "Default")
      (node (ref "LED67") (pin "DO") (pinfunction "DO_DO") (pintype "output"))
      (node (ref "LED68") (pin "DI") (pinfunction "DI_DI") (pintype "input"))
    )
    (net (code "104") (name "Net-(LED68-PadDO)") (class "Default")
      (node (ref "LED68") (pin "DO") (pinfunction "DO_DO") (pintype "output"))
      (node (ref "LED69") (pin "DI") (pinfunction "DI_DI") (pintype "input"))
    )
    (net (code "105") (name "Net-(LED69-PadDO)") (class "Default")
      (node (ref "LED69") (pin "DO") (pinfunction "DO_DO") (pintype "output"))
      (node (ref "LED70") (pin "DI") (pinfunction "DI_DI") (pintype "input"))
    )
    (net (code "106") (name "Net-(LED70-PadDO)") (class "Default")
      (node (ref "LED70") (pin "DO") (pinfunction "DO_DO") (pintype "output"))
      (node (ref "LED71") (pin "DI") (pinfunction "DI_DI") (pintype "input"))
    )
    (net (code "107") (name "Net-(LED71-PadDO)") (class "Default")
      (node (ref "LED71") (pin "DO") (pinfunction "DO_DO") (pintype "output"))
      (node (ref "LED72") (pin "DI") (pinfunction "DI_DI") (pintype "input"))
    )
    (net (code "108") (name "Net-(LED73-PadDO)") (class "Default")
      (node (ref "LED73") (pin "DO") (pinfunction "DO_DO") (pintype "output"))
      (node (ref "LED74") (pin "DI") (pinfunction "DI_DI") (pintype "input"))
    )
    (net (code "109") (name "Net-(LED74-PadDO)") (class "Default")
      (node (ref "LED74") (pin "DO") (pinfunction "DO_DO") (pintype "output"))
      (node (ref "LED75") (pin "DI") (pinfunction "DI_DI") (pintype "input"))
    )
    (net (code "110") (name "Net-(LED75-PadDO)") (class "Default")
      (node (ref "LED75") (pin "DO") (pinfunction "DO_DO") (pintype "output"))
      (node (ref "LED76") (pin "DI") (pinfunction "DI_DI") (pintype "input"))
    )
    (net (code "111") (name "Net-(LED76-PadDO)") (class "Default")
      (node (ref "LED76") (pin "DO") (pinfunction "DO_DO") (pintype "output"))
      (node (ref "LED77") (pin "DI") (pinfunction "DI_DI") (pintype "input"))
    )
    (net (code "112") (name "Net-(LED77-PadDO)") (class "Default")
      (node (ref "LED77") (pin "DO") (pinfunction "DO_DO") (pintype "output"))
      (node (ref "LED78") (pin "DI") (pinfunction "DI_DI") (pintype "input"))
    )
    (net (code "113") (name "Net-(LED78-PadDO)") (class "Default")
      (node (ref "LED78") (pin "DO") (pinfunction "DO_DO") (pintype "output"))
      (node (ref "LED79") (pin "DI") (pinfunction "DI_DI") (pintype "input"))
    )
    (net (code "114") (name "Net-(LED79-PadDO)") (class "Default")
      (node (ref "LED79") (pin "DO") (pinfunction "DO_DO") (pintype "output"))
      (node (ref "LED80") (pin "DI") (pinfunction "DI_DI") (pintype "input"))
    )
    (net (code "115") (name "Net-(LED80-PadDO)") (class "Default")
      (node (ref "LED80") (pin "DO") (pinfunction "DO_DO") (pintype "output"))
      (node (ref "LED81") (pin "DI") (pinfunction "DI_DI") (pintype "input"))
    )
    (net (code "116") (name "Net-(LED81-PadDO)") (class "Default")
      (node (ref "LED81") (pin "DO") (pinfunction "DO_DO") (pintype "output"))
      (node (ref "LED82") (pin "DI") (pinfunction "DI_DI") (pintype "input"))
    )
    (net (code "117") (name "Net-(LED82-PadDO)") (class "Default")
      (node (ref "LED82") (pin "DO") (pinfunction "DO_DO") (pintype "output"))
      (node (ref "LED83") (pin "DI") (pinfunction "DI_DI") (pintype "input"))
    )
    (net (code "118") (name "Net-(LED83-PadDO)") (class "Default")
      (node (ref "LED83") (pin "DO") (pinfunction "DO_DO") (pintype "output"))
      (node (ref "LED84") (pin "DI") (pinfunction "DI_DI") (pintype "input"))
    )
    (net (code "119") (name "Net-(LED84-PadDO)") (class "Default")
      (node (ref "LED84") (pin "DO") (pinfunction "DO_DO") (pintype "output"))
      (node (ref "LED85") (pin "DI") (pinfunction "DI_DI") (pintype "input"))
    )
    (net (code "120") (name "Net-(LED85-PadDO)") (class "Default")
      (node (ref "LED85") (pin "DO") (pinfunction "DO_DO") (pintype "output"))
      (node (ref "LED86") (pin "DI") (pinfunction "DI_DI") (pintype "input"))
    )
    (net (code "121") (name "Net-(LED86-PadDO)") (class "Default")
      (node (ref "LED86") (pin "DO") (pinfunction "DO_DO") (pintype "output"))
      (node (ref "LED87") (pin "DI") (pinfunction "DI_DI") (pintype "input"))
    )
    (net (code "122") (name "Net-(LED87-PadDO)") (class "Default")
      (node (ref "LED87") (pin "DO") (pinfunction "DO_DO") (pintype "output"))
      (node (ref "LED88") (pin "DI") (pinfunction "DI_DI") (pintype "input"))
    )
    (net (code "123") (name "Net-(LED88-PadDO)") (class "Default")
      (node (ref "LED88") (pin "DO") (pinfunction "DO_DO") (pintype "output"))
      (node (ref "LED89") (pin "DI") (pinfunction "DI_DI") (pintype "input"))
    )
    (net (code "124") (name "Net-(LED89-PadDO)") (class "Default")
      (node (ref "LED89") (pin "DO") (pinfunction "DO_DO") (pintype "output"))
      (node (ref "LED90") (pin "DI") (pinfunction "DI_DI") (pintype "input"))
    )
    (net (code "125") (name "Net-(LED90-PadDO)") (class "Default")
      (node (ref "LED90") (pin "DO") (pinfunction "DO_DO") (pintype "output"))
      (node (ref "LED91") (pin "DI") (pinfunction "DI_DI") (pintype "input"))
    )
    (net (code "126") (name "Net-(LED91-PadDO)") (class "Default")
      (node (ref "LED91") (pin "DO") (pinfunction "DO_DO") (pintype "output"))
      (node (ref "LED92") (pin "DI") (pinfunction "DI_DI") (pintype "input"))
    )
    (net (code "127") (name "Net-(LED92-PadDO)") (class "Default")
      (node (ref "LED92") (pin "DO") (pinfunction "DO_DO") (pintype "output"))
      (node (ref "LED93") (pin "DI") (pinfunction "DI_DI") (pintype "input"))
    )
    (net (code "128") (name "Net-(LED93-PadDO)") (class "Default")
      (node (ref "LED93") (pin "DO") (pinfunction "DO_DO") (pintype "output"))
      (node (ref "LED94") (pin "DI") (pinfunction "DI_DI") (pintype "input"))
    )
    (net (code "129") (name "Net-(LED94-PadDO)") (class "Default")
      (node (ref "LED94") (pin "DO") (pinfunction "DO_DO") (pintype "output"))
      (node (ref "LED95") (pin "DI") (pinfunction "DI_DI") (pintype "input"))
    )
    (net (code "130") (name "Net-(LED95-PadDO)") (class "Default")
      (node (ref "LED95") (pin "DO") (pinfunction "DO_DO") (pintype "output"))
      (node (ref "LED96") (pin "DI") (pinfunction "DI_DI") (pintype "input"))
    )
    (net (code "131") (name "Net-(LED96-PadDO)") (class "Default")
      (node (ref "LED96") (pin "DO") (pinfunction "DO_DO") (pintype "output"))
      (node (ref "LED97") (pin "DI") (pinfunction "DI_DI") (pintype "input"))
    )
    (net (code "132") (name "Net-(LED97-PadDO)") (class "Default")
      (node (ref "LED97") (pin "DO") (pinfunction "DO_DO") (pintype "output"))
      (node (ref "LED98") (pin "DI") (pinfunction "DI_DI") (pintype "input"))
    )
    (net (code "133") (name "Net-(LED98-PadDO)") (class "Default")
      (node (ref "LED98") (pin "DO") (pinfunction "DO_DO") (pintype "output"))
      (node (ref "LED99") (pin "DI") (pinfunction "DI_DI") (pintype "input"))
    )
    (net (code "134") (name "Net-(LED100-PadDI)") (class "Default")
      (node (ref "LED100") (pin "DI") (pinfunction "DI_DI") (pintype "input"))
      (node (ref "LED99") (pin "DO") (pinfunction "DO_DO") (pintype "output"))
    )
    (net (code "135") (name "Net-(LED100-PadDO)") (class "Default")
      (node (ref "LED100") (pin "DO") (pinfunction "DO_DO") (pintype "output"))
      (node (ref "LED101") (pin "DI") (pinfunction "DI_DI") (pintype "input"))
    )
    (net (code "136") (name "Net-(LED101-PadDO)") (class "Default")
      (node (ref "LED101") (pin "DO") (pinfunction "DO_DO") (pintype "output"))
      (node (ref "LED102") (pin "DI") (pinfunction "DI_DI") (pintype "input"))
    )
    (net (code "137") (name "Net-(LED102-PadDO)") (class "Default")
      (node (ref "LED102") (pin "DO") (pinfunction "DO_DO") (pintype "output"))
      (node (ref "LED103") (pin "DI") (pinfunction "DI_DI") (pintype "input"))
    )
    (net (code "138") (name "Net-(LED103-PadDO)") (class "Default")
      (node (ref "LED103") (pin "DO") (pinfunction "DO_DO") (pintype "output"))
      (node (ref "LED104") (pin "DI") (pinfunction "DI_DI") (pintype "input"))
    )
    (net (code "139") (name "Net-(LED104-PadDO)") (class "Default")
      (node (ref "LED104") (pin "DO") (pinfunction "DO_DO") (pintype "output"))
      (node (ref "LED105") (pin "DI") (pinfunction "DI_DI") (pintype "input"))
    )
    (net (code "140") (name "Net-(LED105-PadDO)") (class "Default")
      (node (ref "LED105") (pin "DO") (pinfunction "DO_DO") (pintype "output"))
      (node (ref "LED106") (pin "DI") (pinfunction "DI_DI") (pintype "input"))
    )
    (net (code "141") (name "Net-(LED106-PadDO)") (class "Default")
      (node (ref "LED106") (pin "DO") (pinfunction "DO_DO") (pintype "output"))
      (node (ref "LED107") (pin "DI") (pinfunction "DI_DI") (pintype "input"))
    )
    (net (code "142") (name "Net-(LED107-PadDO)") (class "Default")
      (node (ref "LED107") (pin "DO") (pinfunction "DO_DO") (pintype "output"))
      (node (ref "LED108") (pin "DI") (pinfunction "DI_DI") (pintype "input"))
    )
    (net (code "143") (name "Net-(LED108-PadDO)") (class "Default")
      (node (ref "LED108") (pin "DO") (pinfunction "DO_DO") (pintype "output"))
      (node (ref "LED109") (pin "DI") (pinfunction "DI_DI") (pintype "input"))
    )
    (net (code "144") (name "Net-(LED109-PadDO)") (class "Default")
      (node (ref "LED109") (pin "DO") (pinfunction "DO_DO") (pintype "output"))
      (node (ref "LED110") (pin "DI") (pinfunction "DI_DI") (pintype "input"))
    )
    (net (code "145") (name "Net-(LED110-PadDO)") (class "Default")
      (node (ref "LED110") (pin "DO") (pinfunction "DO_DO") (pintype "output"))
      (node (ref "LED111") (pin "DI") (pinfunction "DI_DI") (pintype "input"))
    )
    (net (code "146") (name "Net-(LED111-PadDO)") (class "Default")
      (node (ref "LED111") (pin "DO") (pinfunction "DO_DO") (pintype "output"))
      (node (ref "LED112") (pin "DI") (pinfunction "DI_DI") (pintype "input"))
    )
    (net (code "147") (name "Net-(LED112-PadDO)") (class "Default")
      (node (ref "LED112") (pin "DO") (pinfunction "DO_DO") (pintype "output"))
      (node (ref "LED113") (pin "DI") (pinfunction "DI_DI") (pintype "input"))
    )
    (net (code "148") (name "Net-(LED113-PadDO)") (class "Default")
      (node (ref "LED113") (pin "DO") (pinfunction "DO_DO") (pintype "output"))
      (node (ref "LED114") (pin "DI") (pinfunction "DI_DI") (pintype "input"))
    )
    (net (code "149") (name "Net-(LED114-PadDO)") (class "Default")
      (node (ref "LED114") (pin "DO") (pinfunction "DO_DO") (pintype "output"))
      (node (ref "LED115") (pin "DI") (pinfunction "DI_DI") (pintype "input"))
    )
    (net (code "150") (name "Net-(LED115-PadDO)") (class "Default")
      (node (ref "LED115") (pin "DO") (pinfunction "DO_DO") (pintype "output"))
      (node (ref "LED116") (pin "DI") (pinfunction "DI_DI") (pintype "input"))
    )
    (net (code "151") (name "Net-(LED116-PadDO)") (class "Default")
      (node (ref "LED116") (pin "DO") (pinfunction "DO_DO") (pintype "output"))
      (node (ref "LED117") (pin "DI") (pinfunction "DI_DI") (pintype "input"))
    )
    (net (code "152") (name "Net-(LED117-PadDO)") (class "Default")
      (node (ref "LED117") (pin "DO") (pinfunction "DO_DO") (pintype "output"))
      (node (ref "LED118") (pin "DI") (pinfunction "DI_DI") (pintype "input"))
    )
    (net (code "153") (name "Net-(LED118-PadDO)") (class "Default")
      (node (ref "LED118") (pin "DO") (pinfunction "DO_DO") (pintype "output"))
      (node (ref "LED119") (pin "DI") (pinfunction "DI_DI") (pintype "input"))
    )
    (net (code "154") (name "Net-(LED119-PadDO)") (class "Default")
      (node (ref "LED119") (pin "DO") (pinfunction "DO_DO") (pintype "output"))
      (node (ref "LED120") (pin "DI") (pinfunction "DI_DI") (pintype "input"))
    )
    (net (code "155") (name "Net-(LED120-PadDO)") (class "Default")
      (node (ref "LED120") (pin "DO") (pinfunction "DO_DO") (pintype "output"))
      (node (ref "LED121") (pin "DI") (pinfunction "DI_DI") (pintype "input"))
    )
    (net (code "156") (name "Net-(LED121-PadDO)") (class "Default")
      (node (ref "LED121") (pin "DO") (pinfunction "DO_DO") (pintype "output"))
      (node (ref "LED122") (pin "DI") (pinfunction "DI_DI") (pintype "input"))
    )
    (net (code "157") (name "Net-(LED122-PadDO)") (class "Default")
      (node (ref "LED122") (pin "DO") (pinfunction "DO_DO") (pintype "output"))
      (node (ref "LED123") (pin "DI") (pinfunction "DI_DI") (pintype "input"))
    )
    (net (code "158") (name "Net-(LED123-PadDO)") (class "Default")
      (node (ref "LED123") (pin "DO") (pinfunction "DO_DO") (pintype "output"))
      (node (ref "LED124") (pin "DI") (pinfunction "DI_DI") (pintype "input"))
    )
    (net (code "159") (name "Net-(LED124-PadDO)") (class "Default")
      (node (ref "LED124") (pin "DO") (pinfunction "DO_DO") (pintype "output"))
      (node (ref "LED125") (pin "DI") (pinfunction "DI_DI") (pintype "input"))
    )
    (net (code "160") (name "Net-(LED125-PadDO)") (class "Default")
      (node (ref "LED125") (pin "DO") (pinfunction "DO_DO") (pintype "output"))
      (node (ref "LED126") (pin "DI") (pinfunction "DI_DI") (pintype "input"))
    )
    (net (code "161") (name "Net-(LED126-PadDO)") (class "Default")
      (node (ref "LED126") (pin "DO") (pinfunction "DO_DO") (pintype "output"))
      (node (ref "LED127") (pin "DI") (pinfunction "DI_DI") (pintype "input"))
    )
    (net (code "162") (name "Net-(LED127-PadDO)") (class "Default")
      (node (ref "LED127") (pin "DO") (pinfunction "DO_DO") (pintype "output"))
      (node (ref "LED128") (pin "DI") (pinfunction "DI_DI") (pintype "input"))
    )
    (net (code "163") (name "Net-(LED128-PadDO)") (class "Default")
      (node (ref "LED128") (pin "DO") (pinfunction "DO_DO") (pintype "output"))
      (node (ref "LED129") (pin "DI") (pinfunction "DI_DI") (pintype "input"))
    )
    (net (code "164") (name "Net-(LED129-PadDO)") (class "Default")
      (node (ref "LED129") (pin "DO") (pinfunction "DO_DO") (pintype "output"))
      (node (ref "LED130") (pin "DI") (pinfunction "DI_DI") (pintype "input"))
    )
    (net (code "165") (name "Net-(LED130-PadDO)") (class "Default")
      (node (ref "LED130") (pin "DO") (pinfunction "DO_DO") (pintype "output"))
      (node (ref "LED131") (pin "DI") (pinfunction "DI_DI") (pintype "input"))
    )
    (net (code "166") (name "Net-(LED131-PadDO)") (class "Default")
      (node (ref "LED131") (pin "DO") (pinfunction "DO_DO") (pintype "output"))
      (node (ref "LED132") (pin "DI") (pinfunction "DI_DI") (pintype "input"))
    )
    (net (code "167") (name "Net-(LED132-PadDO)") (class "Default")
      (node (ref "LED132") (pin "DO") (pinfunction "DO_DO") (pintype "output"))
      (node (ref "LED133") (pin "DI") (pinfunction "DI_DI") (pintype "input"))
    )
    (net (code "168") (name "Net-(LED133-PadDO)") (class "Default")
      (node (ref "LED133") (pin "DO") (pinfunction "DO_DO") (pintype "output"))
      (node (ref "LED134") (pin "DI") (pinfunction "DI_DI") (pintype "input"))
    )
    (net (code "169") (name "Net-(LED134-PadDO)") (class "Default")
      (node (ref "LED134") (pin "DO") (pinfunction "DO_DO") (pintype "output"))
      (node (ref "LED135") (pin "DI") (pinfunction "DI_DI") (pintype "input"))
    )
    (net (code "170") (name "Net-(LED135-PadDO)") (class "Default")
      (node (ref "LED135") (pin "DO") (pinfunction "DO_DO") (pintype "output"))
      (node (ref "LED136") (pin "DI") (pinfunction "DI_DI") (pintype "input"))
    )
    (net (code "171") (name "Net-(LED136-PadDO)") (class "Default")
      (node (ref "LED136") (pin "DO") (pinfunction "DO_DO") (pintype "output"))
      (node (ref "LED137") (pin "DI") (pinfunction "DI_DI") (pintype "input"))
    )
    (net (code "172") (name "Net-(LED137-PadDO)") (class "Default")
      (node (ref "LED137") (pin "DO") (pinfunction "DO_DO") (pintype "output"))
      (node (ref "LED138") (pin "DI") (pinfunction "DI_DI") (pintype "input"))
    )
    (net (code "173") (name "Net-(LED138-PadDO)") (class "Default")
      (node (ref "LED138") (pin "DO") (pinfunction "DO_DO") (pintype "output"))
      (node (ref "LED139") (pin "DI") (pinfunction "DI_DI") (pintype "input"))
    )
    (net (code "174") (name "Net-(LED139-PadDO)") (class "Default")
      (node (ref "LED139") (pin "DO") (pinfunction "DO_DO") (pintype "output"))
      (node (ref "LED140") (pin "DI") (pinfunction "DI_DI") (pintype "input"))
    )
    (net (code "175") (name "Net-(LED140-PadDO)") (class "Default")
      (node (ref "LED140") (pin "DO") (pinfunction "DO_DO") (pintype "output"))
      (node (ref "LED141") (pin "DI") (pinfunction "DI_DI") (pintype "input"))
    )
    (net (code "176") (name "Net-(LED141-PadDO)") (class "Default")
      (node (ref "LED141") (pin "DO") (pinfunction "DO_DO") (pintype "output"))
      (node (ref "LED142") (pin "DI") (pinfunction "DI_DI") (pintype "input"))
    )
    (net (code "177") (name "Net-(LED142-PadDO)") (class "Default")
      (node (ref "LED142") (pin "DO") (pinfunction "DO_DO") (pintype "output"))
      (node (ref "LED143") (pin "DI") (pinfunction "DI_DI") (pintype "input"))
    )
    (net (code "178") (name "Net-(LED143-PadDO)") (class "Default")
      (node (ref "LED143") (pin "DO") (pinfunction "DO_DO") (pintype "output"))
      (node (ref "LED144") (pin "DI") (pinfunction "DI_DI") (pintype "input"))
    )
  )
)
